# TK90X.net
KiCad netlist of a schematic drawn in EAGLE
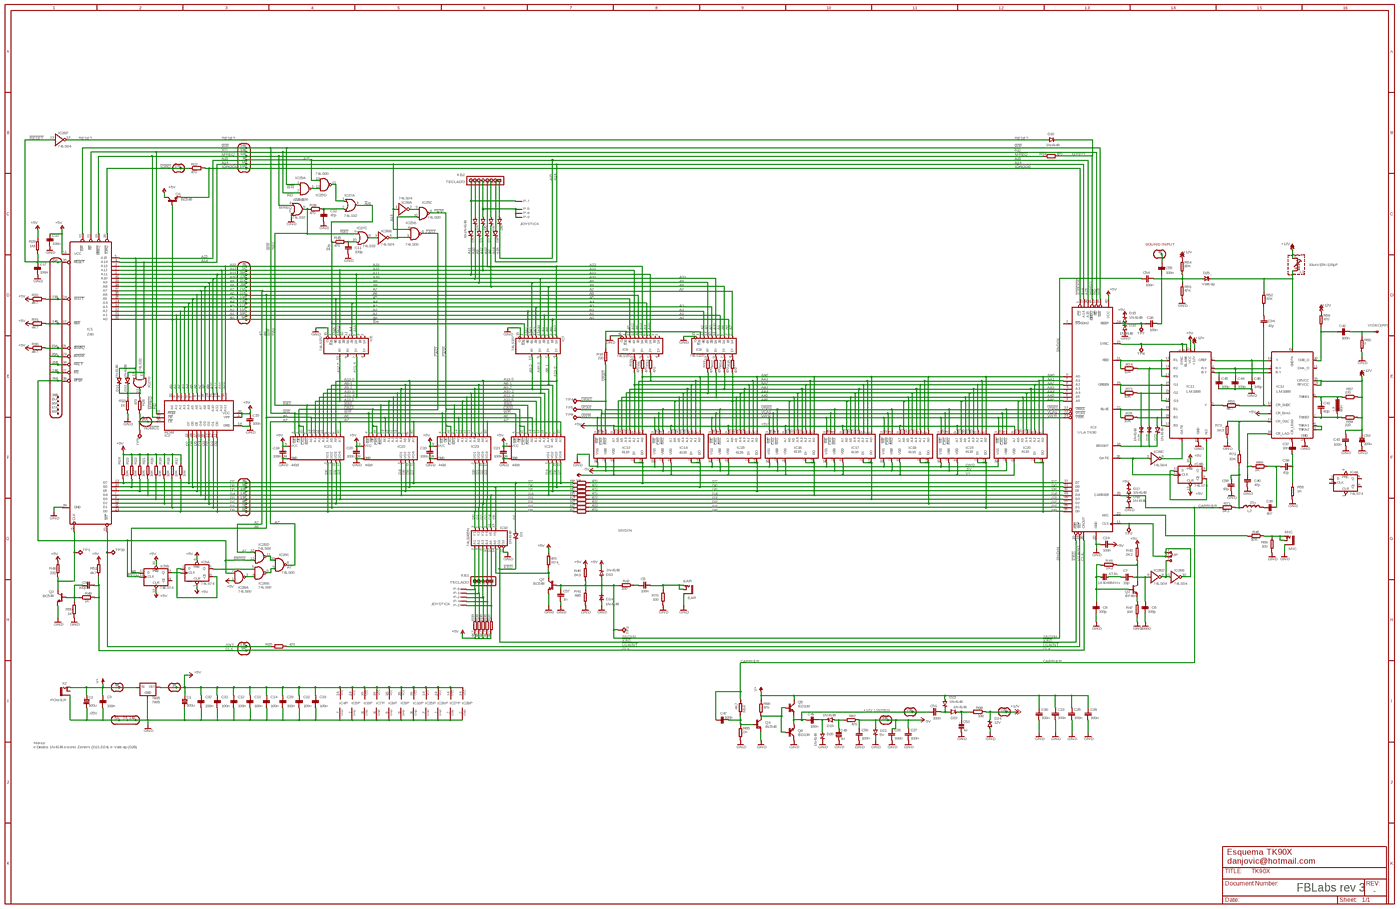
[diagram p0: schematic, sheet 1, overview]
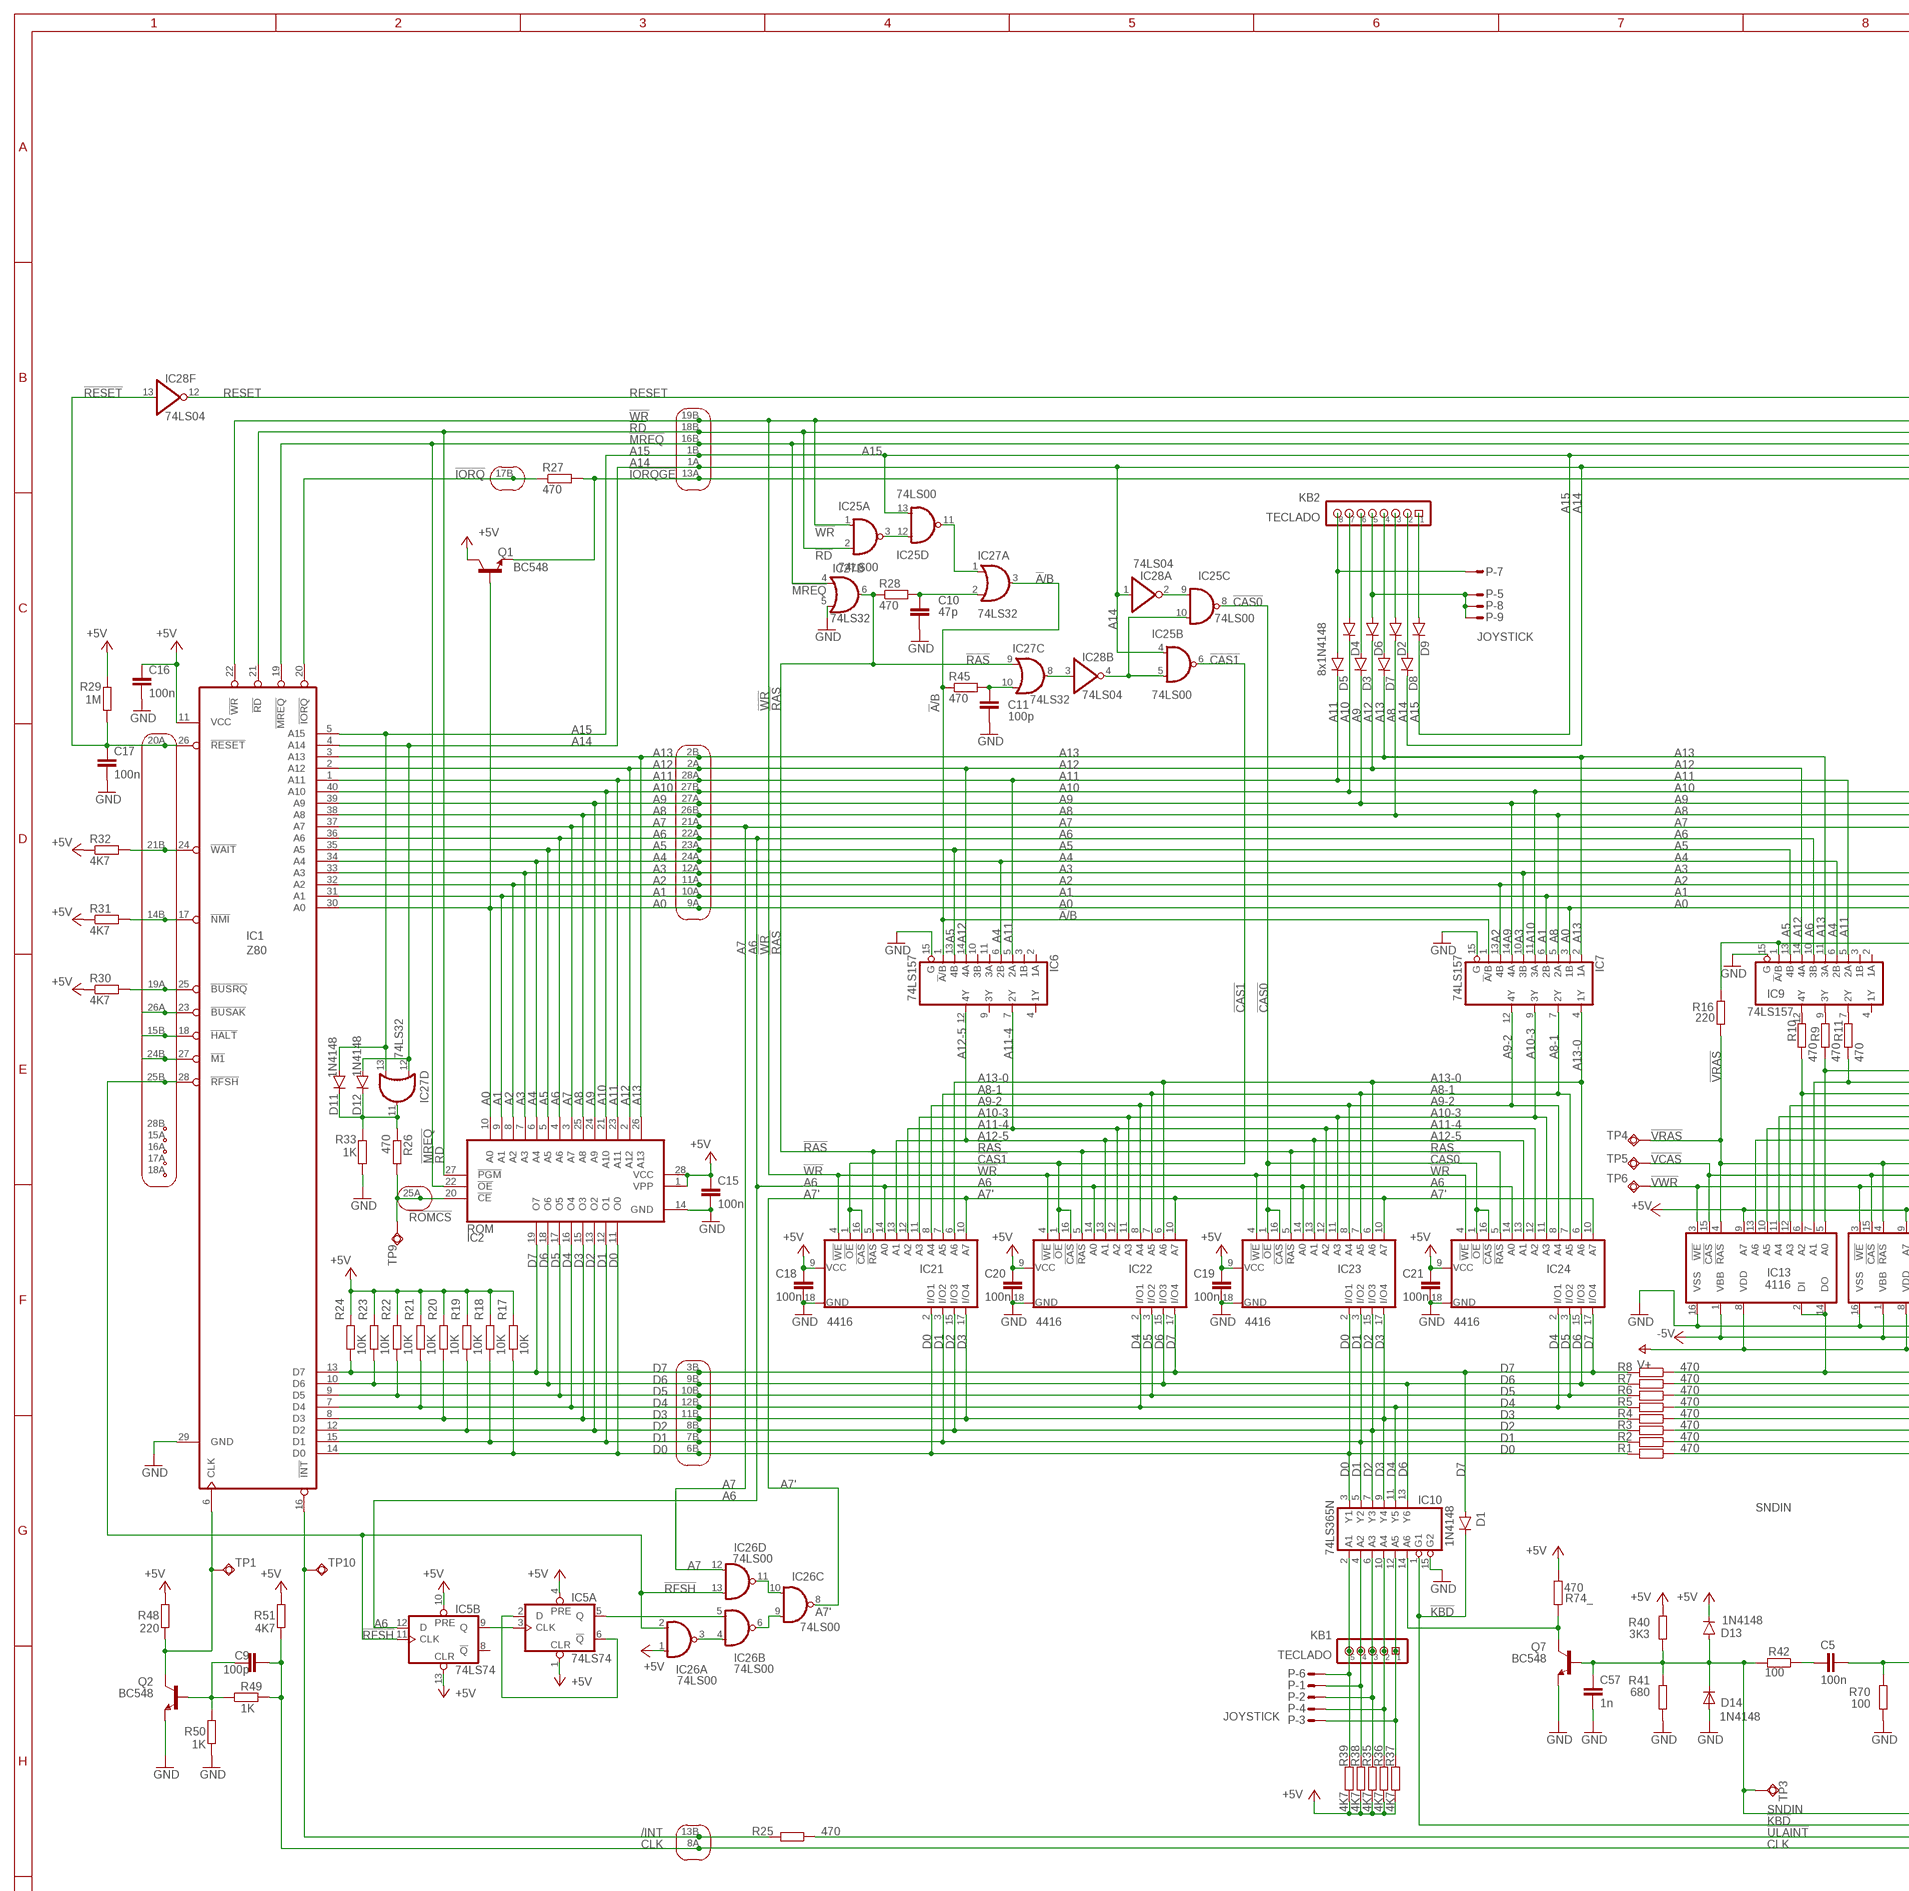
[diagram p1: schematic, sheet 1, part 1 of 4]
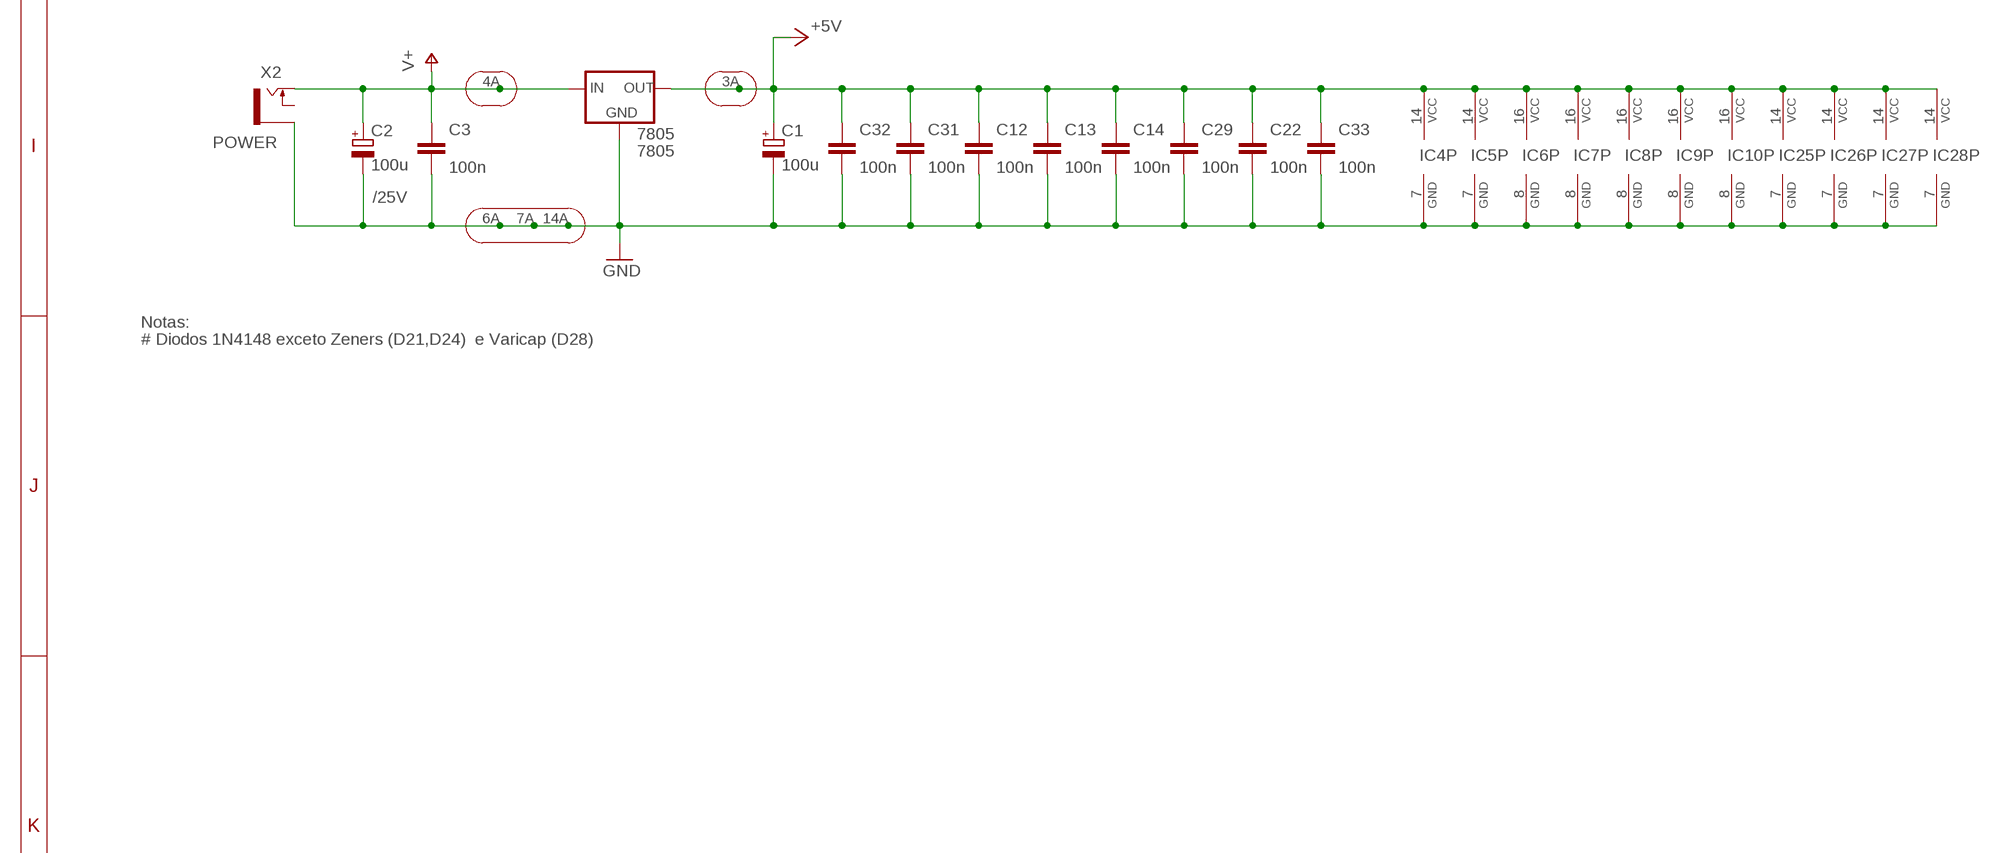
[diagram p2: schematic, sheet 1, part 2 of 4]
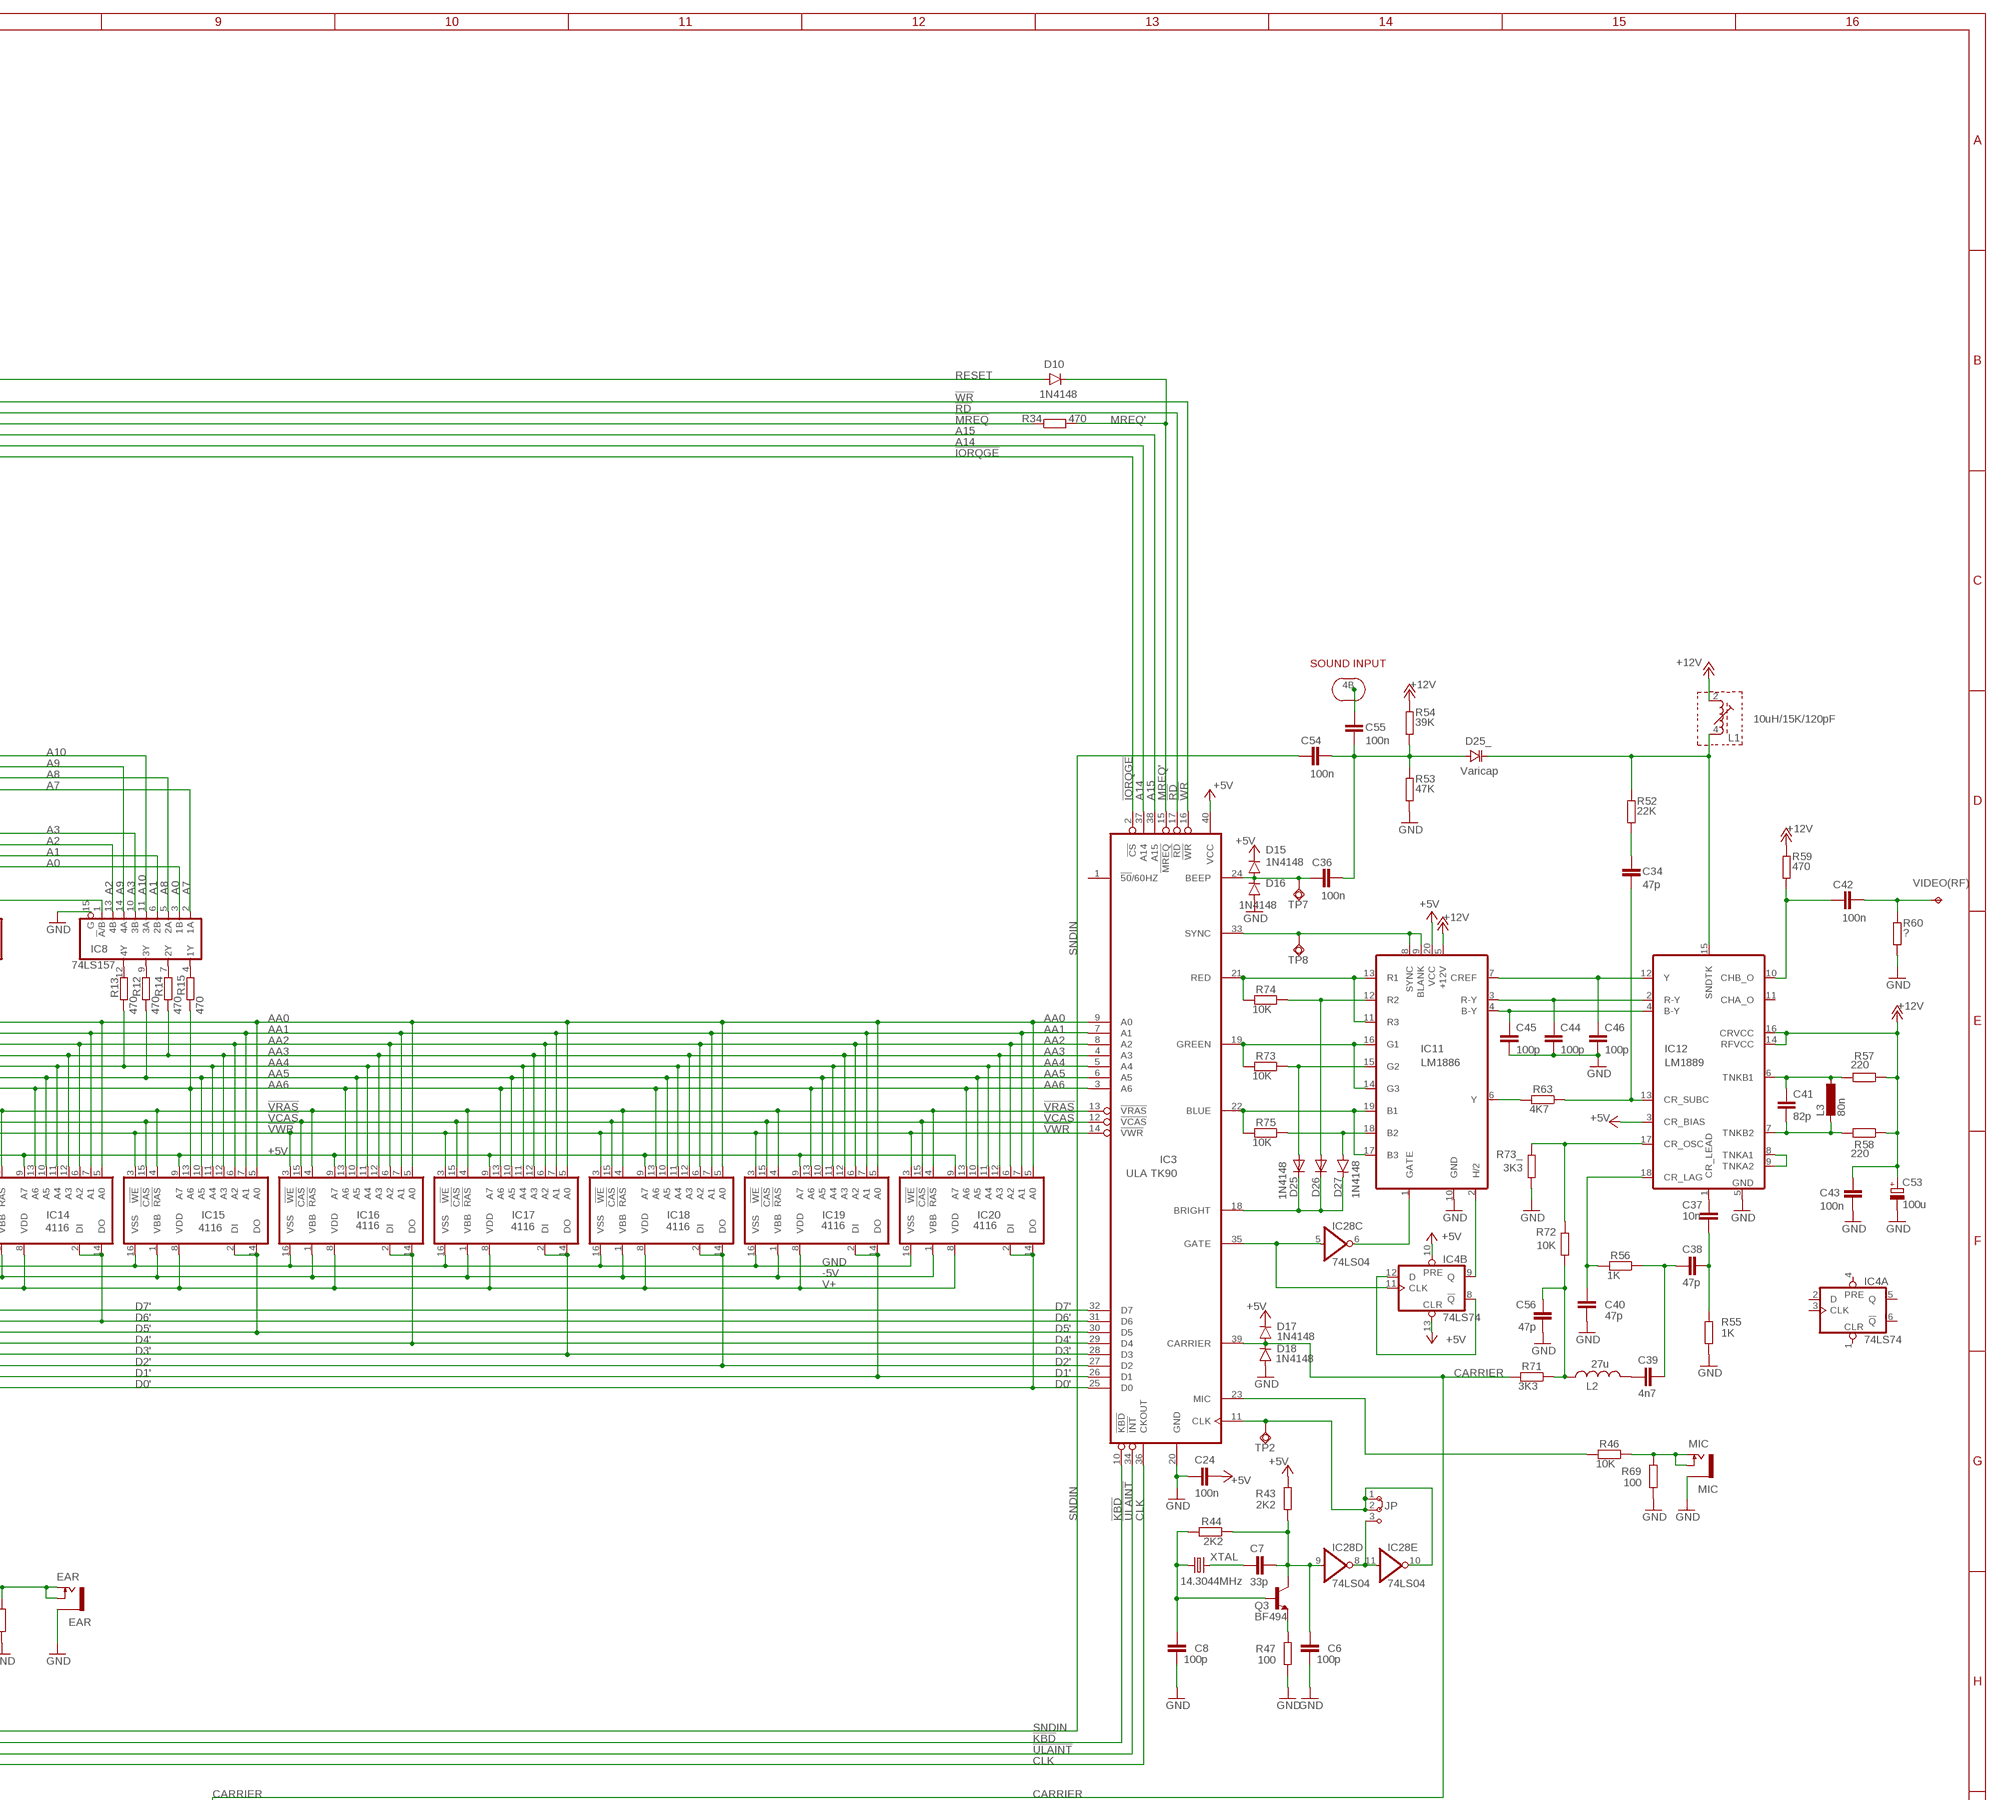
[diagram p3: schematic, sheet 1, part 3 of 4]
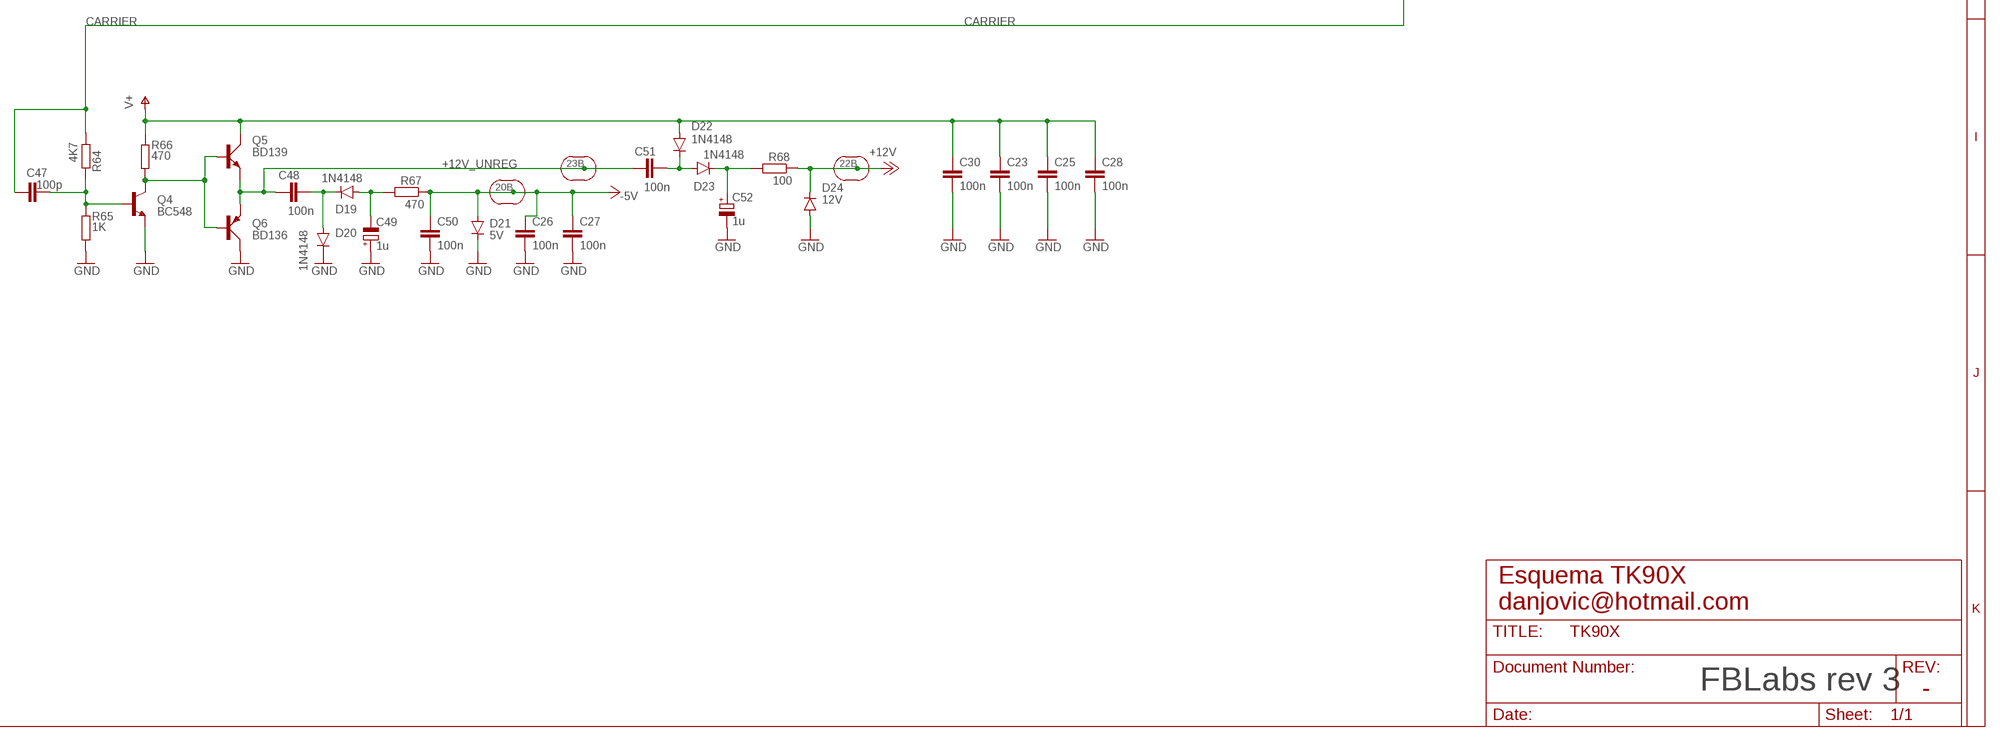
[diagram p4: schematic, sheet 1, part 4 of 4]

(export (version "E")
  (design (tool "Eeschema 10.0.6"))
  (components
    (comp (ref "7805")
      (value "7805")
      (footprint "eagle-import:78XXL")
      (libsource (lib "eagle-import") (part "78XXL"))
    )
    (comp (ref "C1")
      (value "100u")
      (footprint "eagle-import:E5-8,5")
      (libsource (lib "eagle-import") (part "CPOL-EUE5-8.5"))
    )
    (comp (ref "C2")
      (value "100u")
      (footprint "eagle-import:E5-8,5")
      (libsource (lib "eagle-import") (part "CPOL-EUE5-8.5"))
    )
    (comp (ref "C3")
      (value "100n")
      (footprint "eagle-import:C050-024X044")
      (libsource (lib "eagle-import") (part "C-EU050-024X044"))
    )
    (comp (ref "C5")
      (value "100n")
      (footprint "eagle-import:C050-024X044")
      (libsource (lib "eagle-import") (part "C-EU050-024X044"))
    )
    (comp (ref "C6")
      (value "100p")
      (footprint "eagle-import:C050-024X044")
      (libsource (lib "eagle-import") (part "C-EU050-024X044"))
    )
    (comp (ref "C7")
      (value "33p")
      (footprint "eagle-import:C050-024X044")
      (libsource (lib "eagle-import") (part "C-EU050-024X044"))
    )
    (comp (ref "C8")
      (value "100p")
      (footprint "eagle-import:C050-024X044")
      (libsource (lib "eagle-import") (part "C-EU050-024X044"))
    )
    (comp (ref "C9")
      (value "100p")
      (footprint "eagle-import:C050-024X044")
      (libsource (lib "eagle-import") (part "C-EU050-024X044"))
    )
    (comp (ref "C10")
      (value "47p")
      (footprint "eagle-import:C050-024X044")
      (libsource (lib "eagle-import") (part "C-EU050-024X044"))
    )
    (comp (ref "C11")
      (value "100p")
      (footprint "eagle-import:C050-024X044")
      (libsource (lib "eagle-import") (part "C-EU050-024X044"))
    )
    (comp (ref "C12")
      (value "100n")
      (footprint "eagle-import:C050-024X044")
      (libsource (lib "eagle-import") (part "C-EU050-024X044"))
    )
    (comp (ref "C13")
      (value "100n")
      (footprint "eagle-import:C050-024X044")
      (libsource (lib "eagle-import") (part "C-EU050-024X044"))
    )
    (comp (ref "C14")
      (value "100n")
      (footprint "eagle-import:C050-024X044")
      (libsource (lib "eagle-import") (part "C-EU050-024X044"))
    )
    (comp (ref "C15")
      (value "100n")
      (footprint "eagle-import:C050-024X044")
      (libsource (lib "eagle-import") (part "C-EU050-024X044"))
    )
    (comp (ref "C16")
      (value "100n")
      (footprint "eagle-import:C050-024X044")
      (libsource (lib "eagle-import") (part "C-EU050-024X044"))
    )
    (comp (ref "C17")
      (value "100n")
      (footprint "eagle-import:C050-024X044")
      (libsource (lib "eagle-import") (part "C-EU050-024X044"))
    )
    (comp (ref "C18")
      (value "100n")
      (footprint "eagle-import:C050-024X044")
      (libsource (lib "eagle-import") (part "C-EU050-024X044"))
    )
    (comp (ref "C19")
      (value "100n")
      (footprint "eagle-import:C050-024X044")
      (libsource (lib "eagle-import") (part "C-EU050-024X044"))
    )
    (comp (ref "C20")
      (value "100n")
      (footprint "eagle-import:C050-024X044")
      (libsource (lib "eagle-import") (part "C-EU050-024X044"))
    )
    (comp (ref "C21")
      (value "100n")
      (footprint "eagle-import:C050-024X044")
      (libsource (lib "eagle-import") (part "C-EU050-024X044"))
    )
    (comp (ref "C22")
      (value "100n")
      (footprint "eagle-import:C050-024X044")
      (libsource (lib "eagle-import") (part "C-EU050-024X044"))
    )
    (comp (ref "C23")
      (value "100n")
      (footprint "eagle-import:C050-024X044")
      (libsource (lib "eagle-import") (part "C-EU050-024X044"))
    )
    (comp (ref "C24")
      (value "100n")
      (footprint "eagle-import:C050-024X044")
      (libsource (lib "eagle-import") (part "C-EU050-024X044"))
    )
    (comp (ref "C25")
      (value "100n")
      (footprint "eagle-import:C050-024X044")
      (libsource (lib "eagle-import") (part "C-EU050-024X044"))
    )
    (comp (ref "C26")
      (value "100n")
      (footprint "eagle-import:C050-024X044")
      (libsource (lib "eagle-import") (part "C-EU050-024X044"))
    )
    (comp (ref "C27")
      (value "100n")
      (footprint "eagle-import:C050-024X044")
      (libsource (lib "eagle-import") (part "C-EU050-024X044"))
    )
    (comp (ref "C28")
      (value "100n")
      (footprint "eagle-import:C050-024X044")
      (libsource (lib "eagle-import") (part "C-EU050-024X044"))
    )
    (comp (ref "C29")
      (value "100n")
      (footprint "eagle-import:C050-024X044")
      (libsource (lib "eagle-import") (part "C-EU050-024X044"))
    )
    (comp (ref "C30")
      (value "100n")
      (footprint "eagle-import:C050-024X044")
      (libsource (lib "eagle-import") (part "C-EU050-024X044"))
    )
    (comp (ref "C31")
      (value "100n")
      (footprint "eagle-import:C050-024X044")
      (libsource (lib "eagle-import") (part "C-EU050-024X044"))
    )
    (comp (ref "C32")
      (value "100n")
      (footprint "eagle-import:C050-024X044")
      (libsource (lib "eagle-import") (part "C-EU050-024X044"))
    )
    (comp (ref "C33")
      (value "100n")
      (footprint "eagle-import:C050-024X044")
      (libsource (lib "eagle-import") (part "C-EU050-024X044"))
    )
    (comp (ref "C34")
      (value "47p")
      (footprint "eagle-import:C050-024X044")
      (libsource (lib "eagle-import") (part "C-EU050-024X044"))
    )
    (comp (ref "C36")
      (value "100n")
      (footprint "eagle-import:C050-024X044")
      (libsource (lib "eagle-import") (part "C-EU050-024X044"))
    )
    (comp (ref "C37")
      (value "10n")
      (footprint "eagle-import:C050-024X044")
      (libsource (lib "eagle-import") (part "C-EU050-024X044"))
    )
    (comp (ref "C38")
      (value "47p")
      (footprint "eagle-import:C050-024X044")
      (libsource (lib "eagle-import") (part "C-EU050-024X044"))
    )
    (comp (ref "C39")
      (value "4n7")
      (footprint "eagle-import:C050-024X044")
      (libsource (lib "eagle-import") (part "C-EU050-024X044"))
    )
    (comp (ref "C40")
      (value "47p")
      (footprint "eagle-import:C050-024X044")
      (libsource (lib "eagle-import") (part "C-EU050-024X044"))
    )
    (comp (ref "C41")
      (value "82p")
      (footprint "eagle-import:C050-024X044")
      (libsource (lib "eagle-import") (part "C-EU050-024X044"))
    )
    (comp (ref "C42")
      (value "100n")
      (footprint "eagle-import:C050-024X044")
      (libsource (lib "eagle-import") (part "C-EU050-024X044"))
    )
    (comp (ref "C43")
      (value "100n")
      (footprint "eagle-import:C050-024X044")
      (libsource (lib "eagle-import") (part "C-EU050-024X044"))
    )
    (comp (ref "C44")
      (value "100p")
      (footprint "eagle-import:C050-024X044")
      (libsource (lib "eagle-import") (part "C-EU050-024X044"))
    )
    (comp (ref "C45")
      (value "100p")
      (footprint "eagle-import:C050-024X044")
      (libsource (lib "eagle-import") (part "C-EU050-024X044"))
    )
    (comp (ref "C46")
      (value "100p")
      (footprint "eagle-import:C050-024X044")
      (libsource (lib "eagle-import") (part "C-EU050-024X044"))
    )
    (comp (ref "C47")
      (value "100p")
      (footprint "eagle-import:C050-024X044")
      (libsource (lib "eagle-import") (part "C-EU050-024X044"))
    )
    (comp (ref "C48")
      (value "100n")
      (footprint "eagle-import:C050-024X044")
      (libsource (lib "eagle-import") (part "C-EU050-024X044"))
    )
    (comp (ref "C49")
      (value "1u")
      (footprint "eagle-import:E2-4")
      (libsource (lib "eagle-import") (part "CPOL-EUE2-4"))
    )
    (comp (ref "C50")
      (value "100n")
      (footprint "eagle-import:C050-024X044")
      (libsource (lib "eagle-import") (part "C-EU050-024X044"))
    )
    (comp (ref "C51")
      (value "100n")
      (footprint "eagle-import:C050-024X044")
      (libsource (lib "eagle-import") (part "C-EU050-024X044"))
    )
    (comp (ref "C52")
      (value "1u")
      (footprint "eagle-import:E2-5")
      (libsource (lib "eagle-import") (part "CPOL-EUE2-5"))
    )
    (comp (ref "C53")
      (value "100u")
      (footprint "eagle-import:E5-4")
      (libsource (lib "eagle-import") (part "CPOL-EUE5-4"))
    )
    (comp (ref "C54")
      (value "100n")
      (footprint "eagle-import:C050-024X044")
      (libsource (lib "eagle-import") (part "C-EU050-024X044"))
    )
    (comp (ref "C55")
      (value "100n")
      (footprint "eagle-import:C050-024X044")
      (libsource (lib "eagle-import") (part "C-EU050-024X044"))
    )
    (comp (ref "C56")
      (value "47p")
      (footprint "eagle-import:C050-024X044")
      (libsource (lib "eagle-import") (part "C-EU050-024X044"))
    )
    (comp (ref "C57")
      (value "1n")
      (footprint "eagle-import:C050-024X044")
      (libsource (lib "eagle-import") (part "C-EU050-024X044"))
    )
    (comp (ref "D1")
      (value "1N4148")
      (footprint "eagle-import:DO35-12")
      (libsource (lib "eagle-import") (part "DDO35-12"))
    )
    (comp (ref "D2")
      (value "1N4148")
      (footprint "eagle-import:DO35-12")
      (libsource (lib "eagle-import") (part "DDO35-12"))
    )
    (comp (ref "D3")
      (value "1N4148")
      (footprint "eagle-import:DO35-12")
      (libsource (lib "eagle-import") (part "DDO35-12"))
    )
    (comp (ref "D4")
      (value "1N4148")
      (footprint "eagle-import:DO35-12")
      (libsource (lib "eagle-import") (part "DDO35-12"))
    )
    (comp (ref "D5")
      (value "1N4148")
      (footprint "eagle-import:DO35-12")
      (libsource (lib "eagle-import") (part "DDO35-12"))
    )
    (comp (ref "D6")
      (value "1N4148")
      (footprint "eagle-import:DO35-12")
      (libsource (lib "eagle-import") (part "DDO35-12"))
    )
    (comp (ref "D7")
      (value "1N4148")
      (footprint "eagle-import:DO35-12")
      (libsource (lib "eagle-import") (part "DDO35-12"))
    )
    (comp (ref "D8")
      (value "1N4148")
      (footprint "eagle-import:DO35-12")
      (libsource (lib "eagle-import") (part "DDO35-12"))
    )
    (comp (ref "D9")
      (value "1N4148")
      (footprint "eagle-import:DO35-12")
      (libsource (lib "eagle-import") (part "DDO35-12"))
    )
    (comp (ref "D10")
      (value "1N4148")
      (footprint "eagle-import:DO35-12")
      (libsource (lib "eagle-import") (part "DDO35-12"))
    )
    (comp (ref "D11")
      (value "1N4148")
      (footprint "eagle-import:DO35-12")
      (libsource (lib "eagle-import") (part "DDO35-12"))
    )
    (comp (ref "D12")
      (value "1N4148")
      (footprint "eagle-import:DO35-12")
      (libsource (lib "eagle-import") (part "DDO35-12"))
    )
    (comp (ref "D13")
      (value "1N4148")
      (footprint "eagle-import:DO35-12")
      (libsource (lib "eagle-import") (part "DDO35-12"))
    )
    (comp (ref "D14")
      (value "1N4148")
      (footprint "eagle-import:D-5")
      (libsource (lib "eagle-import") (part "DIODE-D-5"))
    )
    (comp (ref "D15")
      (value "1N4148")
      (footprint "eagle-import:DO35-12")
      (libsource (lib "eagle-import") (part "DDO35-12"))
    )
    (comp (ref "D16")
      (value "1N4148")
      (footprint "eagle-import:DO35-12")
      (libsource (lib "eagle-import") (part "DDO35-12"))
    )
    (comp (ref "D17")
      (value "1N4148")
      (footprint "eagle-import:DO35-12")
      (libsource (lib "eagle-import") (part "DDO35-12"))
    )
    (comp (ref "D18")
      (value "1N4148")
      (footprint "eagle-import:DO35-12")
      (libsource (lib "eagle-import") (part "DDO35-12"))
    )
    (comp (ref "D19")
      (value "1N4148")
      (footprint "eagle-import:DO35-12")
      (libsource (lib "eagle-import") (part "DDO35-12"))
    )
    (comp (ref "D20")
      (value "1N4148")
      (footprint "eagle-import:DO35-12")
      (libsource (lib "eagle-import") (part "DDO35-12"))
    )
    (comp (ref "D21")
      (value "5V")
      (footprint "eagle-import:DO35-12")
      (libsource (lib "eagle-import") (part "DDO35-12"))
    )
    (comp (ref "D22")
      (value "1N4148")
      (footprint "eagle-import:DO35-12")
      (libsource (lib "eagle-import") (part "DDO35-12"))
    )
    (comp (ref "D23")
      (value "1N4148")
      (footprint "eagle-import:DO35-12")
      (libsource (lib "eagle-import") (part "DDO35-12"))
    )
    (comp (ref "D24")
      (value "12V")
      (footprint "eagle-import:DO35-12")
      (libsource (lib "eagle-import") (part "DDO35-12"))
    )
    (comp (ref "D25")
      (value "1N4148")
      (footprint "eagle-import:D-5")
      (libsource (lib "eagle-import") (part "DIODE-D-5"))
    )
    (comp (ref "D25_")
      (value "Varicap")
      (footprint "eagle-import:D200")
      (libsource (lib "eagle-import") (part "VARICAP-200"))
    )
    (comp (ref "D26")
      (value "1N4148")
      (footprint "eagle-import:D-5")
      (libsource (lib "eagle-import") (part "DIODE-D-5"))
    )
    (comp (ref "D27")
      (value "1N4148")
      (footprint "eagle-import:DO35-12")
      (libsource (lib "eagle-import") (part "DDO35-12"))
    )
    (comp (ref "EAR")
      (value "EAR")
      (footprint "eagle-import:MONO")
      (libsource (lib "eagle-import") (part "JACK?-MONO"))
    )
    (comp (ref "IC1")
      (value "Z80")
      (footprint "eagle-import:DIL40")
      (libsource (lib "eagle-import") (part "Z80CPU"))
    )
    (comp (ref "IC2")
      (value "ROM")
      (footprint "eagle-import:DIL28")
      (libsource (lib "eagle-import") (part "25128"))
    )
    (comp (ref "IC3")
      (value "ULA TK90")
      (footprint "eagle-import:DIL40")
      (libsource (lib "eagle-import") (part "ULA-TK90"))
    )
    (comp (ref "IC4")
      (value "74LS74")
      (footprint "eagle-import:DIL14")
      (libsource (lib "eagle-import") (part "7474NLS"))
    )
    (comp (ref "IC5")
      (value "74LS74")
      (footprint "eagle-import:DIL14")
      (libsource (lib "eagle-import") (part "7474NLS"))
    )
    (comp (ref "IC6")
      (value "74LS157")
      (footprint "eagle-import:DIL16")
      (libsource (lib "eagle-import") (part "74157NS"))
    )
    (comp (ref "IC7")
      (value "74LS157")
      (footprint "eagle-import:DIL16")
      (libsource (lib "eagle-import") (part "74157NS"))
    )
    (comp (ref "IC8")
      (value "74LS157")
      (footprint "eagle-import:DIL16")
      (libsource (lib "eagle-import") (part "74157NS"))
    )
    (comp (ref "IC9")
      (value "74LS157")
      (footprint "eagle-import:DIL16")
      (libsource (lib "eagle-import") (part "74157NS"))
    )
    (comp (ref "IC10")
      (value "74LS365N")
      (footprint "eagle-import:DIL16")
      (libsource (lib "eagle-import") (part "74365NLS"))
    )
    (comp (ref "IC11")
      (value "LM1886")
      (footprint "eagle-import:DIL20")
      (libsource (lib "eagle-import") (part "LM1886N"))
    )
    (comp (ref "IC12")
      (value "LM1889")
      (footprint "eagle-import:DIL18")
      (libsource (lib "eagle-import") (part "LM1889"))
    )
    (comp (ref "IC13")
      (value "4116")
      (footprint "eagle-import:DIL16")
      (libsource (lib "eagle-import") (part "MK4516"))
    )
    (comp (ref "IC14")
      (value "4116")
      (footprint "eagle-import:DIL16")
      (libsource (lib "eagle-import") (part "MK4516"))
    )
    (comp (ref "IC15")
      (value "4116")
      (footprint "eagle-import:DIL16")
      (libsource (lib "eagle-import") (part "MK4516"))
    )
    (comp (ref "IC16")
      (value "4116")
      (footprint "eagle-import:DIL16")
      (libsource (lib "eagle-import") (part "MK4516"))
    )
    (comp (ref "IC17")
      (value "4116")
      (footprint "eagle-import:DIL16")
      (libsource (lib "eagle-import") (part "MK4516"))
    )
    (comp (ref "IC18")
      (value "4116")
      (footprint "eagle-import:DIL16")
      (libsource (lib "eagle-import") (part "MK4516"))
    )
    (comp (ref "IC19")
      (value "4116")
      (footprint "eagle-import:DIL16")
      (libsource (lib "eagle-import") (part "MK4516"))
    )
    (comp (ref "IC20")
      (value "4116")
      (footprint "eagle-import:DIL16")
      (libsource (lib "eagle-import") (part "MK4516"))
    )
    (comp (ref "IC21")
      (value "4416")
      (footprint "eagle-import:DIL18")
      (libsource (lib "eagle-import") (part "4416"))
    )
    (comp (ref "IC22")
      (value "4416")
      (footprint "eagle-import:DIL18")
      (libsource (lib "eagle-import") (part "4416"))
    )
    (comp (ref "IC23")
      (value "4416")
      (footprint "eagle-import:DIL18")
      (libsource (lib "eagle-import") (part "4416"))
    )
    (comp (ref "IC24")
      (value "4416")
      (footprint "eagle-import:DIL18")
      (libsource (lib "eagle-import") (part "4416"))
    )
    (comp (ref "IC25")
      (value "74LS00")
      (footprint "eagle-import:DIL14")
      (libsource (lib "eagle-import") (part "7400NLS"))
    )
    (comp (ref "IC26")
      (value "74LS00")
      (footprint "eagle-import:DIL14")
      (libsource (lib "eagle-import") (part "7400NLS"))
    )
    (comp (ref "IC27")
      (value "74LS32")
      (footprint "eagle-import:DIL14")
      (libsource (lib "eagle-import") (part "7432NLS"))
    )
    (comp (ref "IC28")
      (value "74LS04")
      (footprint "eagle-import:DIL14")
      (libsource (lib "eagle-import") (part "7404NLS"))
    )
    (comp (ref "JP")
      (value "J2X1MM")
      (footprint "eagle-import:03C")
      (libsource (lib "eagle-import") (part "J2X1MM"))
    )
    (comp (ref "KB1")
      (value "TECLADO")
      (footprint "eagle-import:FE05-1")
      (libsource (lib "eagle-import") (part "CON-TECL-5"))
    )
    (comp (ref "KB2")
      (value "TECLADO")
      (footprint "eagle-import:FE08")
      (libsource (lib "eagle-import") (part "CON-TECL-8"))
    )
    (comp (ref "L1")
      (value "10uH/15K/120pF")
      (footprint "eagle-import:COIL")
      (libsource (lib "eagle-import") (part "COIL"))
    )
    (comp (ref "L2")
      (value "27u")
      (footprint "eagle-import:0207_7")
      (libsource (lib "eagle-import") (part "L-US0207/7"))
    )
    (comp (ref "L3")
      (value "80n")
      (footprint "eagle-import:0204_5")
      (libsource (lib "eagle-import") (part "L-EU0204/5"))
    )
    (comp (ref "MIC")
      (value "MIC")
      (footprint "eagle-import:MONO")
      (libsource (lib "eagle-import") (part "JACK?-MONO"))
    )
    (comp (ref "P")
      (value "JOYSTICK")
      (footprint "eagle-import:177-009-MALE")
      (libsource (lib "eagle-import") (part "M09?S.590"))
    )
    (comp (ref "Q1")
      (value "BC548")
      (footprint "eagle-import:TO92L")
      (libsource (lib "eagle-import") (part "-NPN-TO92L"))
    )
    (comp (ref "Q2")
      (value "BC548")
      (footprint "eagle-import:TO92L")
      (libsource (lib "eagle-import") (part "-NPN-TO92L"))
    )
    (comp (ref "Q3")
      (value "BF494")
      (footprint "eagle-import:TO92-CEB")
      (libsource (lib "eagle-import") (part "BF494"))
    )
    (comp (ref "Q4")
      (value "BC548")
      (footprint "eagle-import:TO92L")
      (libsource (lib "eagle-import") (part "-NPN-TO92L"))
    )
    (comp (ref "Q5")
      (value "BD139")
      (footprint "eagle-import:TO126AV")
      (libsource (lib "eagle-import") (part "BD139"))
    )
    (comp (ref "Q6")
      (value "BD136")
      (footprint "eagle-import:TO126AV")
      (libsource (lib "eagle-import") (part "BD140"))
    )
    (comp (ref "Q7")
      (value "BC548")
      (footprint "eagle-import:TO92L")
      (libsource (lib "eagle-import") (part "-NPN-TO92L"))
    )
    (comp (ref "R1")
      (value "470")
      (footprint "eagle-import:0207_12")
      (libsource (lib "eagle-import") (part "R-EU_0207/12"))
    )
    (comp (ref "R2")
      (value "470")
      (footprint "eagle-import:0207_12")
      (libsource (lib "eagle-import") (part "R-EU_0207/12"))
    )
    (comp (ref "R3")
      (value "470")
      (footprint "eagle-import:0207_12")
      (libsource (lib "eagle-import") (part "R-EU_0207/12"))
    )
    (comp (ref "R4")
      (value "470")
      (footprint "eagle-import:0207_12")
      (libsource (lib "eagle-import") (part "R-EU_0207/12"))
    )
    (comp (ref "R5")
      (value "470")
      (footprint "eagle-import:0207_12")
      (libsource (lib "eagle-import") (part "R-EU_0207/12"))
    )
    (comp (ref "R6")
      (value "470")
      (footprint "eagle-import:0207_12")
      (libsource (lib "eagle-import") (part "R-EU_0207/12"))
    )
    (comp (ref "R7")
      (value "470")
      (footprint "eagle-import:0207_12")
      (libsource (lib "eagle-import") (part "R-EU_0207/12"))
    )
    (comp (ref "R8")
      (value "470")
      (footprint "eagle-import:0207_12")
      (libsource (lib "eagle-import") (part "R-EU_0207/12"))
    )
    (comp (ref "R9")
      (value "470")
      (footprint "eagle-import:0207_12")
      (libsource (lib "eagle-import") (part "R-EU_0207/12"))
    )
    (comp (ref "R10")
      (value "470")
      (footprint "eagle-import:0207_12")
      (libsource (lib "eagle-import") (part "R-EU_0207/12"))
    )
    (comp (ref "R11")
      (value "470")
      (footprint "eagle-import:0207_12")
      (libsource (lib "eagle-import") (part "R-EU_0207/12"))
    )
    (comp (ref "R12")
      (value "470")
      (footprint "eagle-import:0207_12")
      (libsource (lib "eagle-import") (part "R-EU_0207/12"))
    )
    (comp (ref "R13")
      (value "470")
      (footprint "eagle-import:0207_12")
      (libsource (lib "eagle-import") (part "R-EU_0207/12"))
    )
    (comp (ref "R14")
      (value "470")
      (footprint "eagle-import:0207_12")
      (libsource (lib "eagle-import") (part "R-EU_0207/12"))
    )
    (comp (ref "R15")
      (value "470")
      (footprint "eagle-import:0207_12")
      (libsource (lib "eagle-import") (part "R-EU_0207/12"))
    )
    (comp (ref "R16")
      (value "220")
      (footprint "eagle-import:0207_12")
      (libsource (lib "eagle-import") (part "R-EU_0207/12"))
    )
    (comp (ref "R17")
      (value "10K")
      (footprint "eagle-import:0207_12")
      (libsource (lib "eagle-import") (part "R-EU_0207/12"))
    )
    (comp (ref "R18")
      (value "10K")
      (footprint "eagle-import:0207_12")
      (libsource (lib "eagle-import") (part "R-EU_0207/12"))
    )
    (comp (ref "R19")
      (value "10K")
      (footprint "eagle-import:0207_12")
      (libsource (lib "eagle-import") (part "R-EU_0207/12"))
    )
    (comp (ref "R20")
      (value "10K")
      (footprint "eagle-import:0207_12")
      (libsource (lib "eagle-import") (part "R-EU_0207/12"))
    )
    (comp (ref "R21")
      (value "10K")
      (footprint "eagle-import:0207_12")
      (libsource (lib "eagle-import") (part "R-EU_0207/12"))
    )
    (comp (ref "R22")
      (value "10K")
      (footprint "eagle-import:0207_12")
      (libsource (lib "eagle-import") (part "R-EU_0207/12"))
    )
    (comp (ref "R23")
      (value "10K")
      (footprint "eagle-import:0207_12")
      (libsource (lib "eagle-import") (part "R-EU_0207/12"))
    )
    (comp (ref "R24")
      (value "10K")
      (footprint "eagle-import:0207_12")
      (libsource (lib "eagle-import") (part "R-EU_0207/12"))
    )
    (comp (ref "R25")
      (value "470")
      (footprint "eagle-import:0207_12")
      (libsource (lib "eagle-import") (part "R-EU_0207/12"))
    )
    (comp (ref "R26")
      (value "470")
      (footprint "eagle-import:0207_12")
      (libsource (lib "eagle-import") (part "R-EU_0207/12"))
    )
    (comp (ref "R27")
      (value "470")
      (footprint "eagle-import:0207_12")
      (libsource (lib "eagle-import") (part "R-EU_0207/12"))
    )
    (comp (ref "R28")
      (value "470")
      (footprint "eagle-import:0207_12")
      (libsource (lib "eagle-import") (part "R-EU_0207/12"))
    )
    (comp (ref "R29")
      (value "1M")
      (footprint "eagle-import:0207_12")
      (libsource (lib "eagle-import") (part "R-EU_0207/12"))
    )
    (comp (ref "R30")
      (value "4K7")
      (footprint "eagle-import:0207_12")
      (libsource (lib "eagle-import") (part "R-EU_0207/12"))
    )
    (comp (ref "R31")
      (value "4K7")
      (footprint "eagle-import:0207_12")
      (libsource (lib "eagle-import") (part "R-EU_0207/12"))
    )
    (comp (ref "R32")
      (value "4K7")
      (footprint "eagle-import:0207_12")
      (libsource (lib "eagle-import") (part "R-EU_0207/12"))
    )
    (comp (ref "R33")
      (value "1K")
      (footprint "eagle-import:0207_12")
      (libsource (lib "eagle-import") (part "R-EU_0207/12"))
    )
    (comp (ref "R34")
      (value "470")
      (footprint "eagle-import:0207_12")
      (libsource (lib "eagle-import") (part "R-EU_0207/12"))
    )
    (comp (ref "R35")
      (value "4K7")
      (footprint "eagle-import:0207_12")
      (libsource (lib "eagle-import") (part "R-EU_0207/12"))
    )
    (comp (ref "R36")
      (value "4K7")
      (footprint "eagle-import:0207_12")
      (libsource (lib "eagle-import") (part "R-EU_0207/12"))
    )
    (comp (ref "R37")
      (value "4K7")
      (footprint "eagle-import:0207_12")
      (libsource (lib "eagle-import") (part "R-EU_0207/12"))
    )
    (comp (ref "R38")
      (value "4K7")
      (footprint "eagle-import:0207_12")
      (libsource (lib "eagle-import") (part "R-EU_0207/12"))
    )
    (comp (ref "R39")
      (value "4K7")
      (footprint "eagle-import:0207_12")
      (libsource (lib "eagle-import") (part "R-EU_0207/12"))
    )
    (comp (ref "R40")
      (value "3K3")
      (footprint "eagle-import:0207_12")
      (libsource (lib "eagle-import") (part "R-EU_0207/12"))
    )
    (comp (ref "R41")
      (value "680")
      (footprint "eagle-import:0207_5V")
      (libsource (lib "eagle-import") (part "R-EU_0207/5V"))
    )
    (comp (ref "R42")
      (value "100")
      (footprint "eagle-import:0207_5V")
      (libsource (lib "eagle-import") (part "R-EU_0207/5V"))
    )
    (comp (ref "R43")
      (value "2K2")
      (footprint "eagle-import:0207_12")
      (libsource (lib "eagle-import") (part "R-EU_0207/12"))
    )
    (comp (ref "R44")
      (value "2K2")
      (footprint "eagle-import:0207_12")
      (libsource (lib "eagle-import") (part "R-EU_0207/12"))
    )
    (comp (ref "R45")
      (value "470")
      (footprint "eagle-import:0207_12")
      (libsource (lib "eagle-import") (part "R-EU_0207/12"))
    )
    (comp (ref "R46")
      (value "10K")
      (footprint "eagle-import:0207_12")
      (libsource (lib "eagle-import") (part "R-EU_0207/12"))
    )
    (comp (ref "R47")
      (value "100")
      (footprint "eagle-import:0207_12")
      (libsource (lib "eagle-import") (part "R-EU_0207/12"))
    )
    (comp (ref "R48")
      (value "220")
      (footprint "eagle-import:0207_12")
      (libsource (lib "eagle-import") (part "R-EU_0207/12"))
    )
    (comp (ref "R49")
      (value "1K")
      (footprint "eagle-import:0207_12")
      (libsource (lib "eagle-import") (part "R-EU_0207/12"))
    )
    (comp (ref "R50")
      (value "1K")
      (footprint "eagle-import:0207_12")
      (libsource (lib "eagle-import") (part "R-EU_0207/12"))
    )
    (comp (ref "R51")
      (value "4K7")
      (footprint "eagle-import:0207_12")
      (libsource (lib "eagle-import") (part "R-EU_0207/12"))
    )
    (comp (ref "R52")
      (value "22K")
      (footprint "eagle-import:0207_5V")
      (libsource (lib "eagle-import") (part "R-EU_0207/5V"))
    )
    (comp (ref "R53")
      (value "47K")
      (footprint "eagle-import:0207_12")
      (libsource (lib "eagle-import") (part "R-EU_0207/12"))
    )
    (comp (ref "R54")
      (value "39K")
      (footprint "eagle-import:0207_12")
      (libsource (lib "eagle-import") (part "R-EU_0207/12"))
    )
    (comp (ref "R55")
      (value "1K")
      (footprint "eagle-import:0207_5V")
      (libsource (lib "eagle-import") (part "R-EU_0207/5V"))
    )
    (comp (ref "R56")
      (value "1K")
      (footprint "eagle-import:0207_5V")
      (libsource (lib "eagle-import") (part "R-EU_0207/5V"))
    )
    (comp (ref "R57")
      (value "220")
      (footprint "eagle-import:0207_5V")
      (libsource (lib "eagle-import") (part "R-EU_0207/5V"))
    )
    (comp (ref "R58")
      (value "220")
      (footprint "eagle-import:0207_5V")
      (libsource (lib "eagle-import") (part "R-EU_0207/5V"))
    )
    (comp (ref "R59")
      (value "470")
      (footprint "eagle-import:0207_5V")
      (libsource (lib "eagle-import") (part "R-EU_0207/5V"))
    )
    (comp (ref "R60")
      (value "?")
      (footprint "eagle-import:0207_5V")
      (libsource (lib "eagle-import") (part "R-EU_0207/5V"))
    )
    (comp (ref "R63")
      (value "4K7")
      (footprint "eagle-import:0207_12")
      (libsource (lib "eagle-import") (part "R-EU_0207/12"))
    )
    (comp (ref "R64")
      (value "4K7")
      (footprint "eagle-import:0207_12")
      (libsource (lib "eagle-import") (part "R-EU_0207/12"))
    )
    (comp (ref "R65")
      (value "1K")
      (footprint "eagle-import:0207_12")
      (libsource (lib "eagle-import") (part "R-EU_0207/12"))
    )
    (comp (ref "R66")
      (value "470")
      (footprint "eagle-import:0207_12")
      (libsource (lib "eagle-import") (part "R-EU_0207/12"))
    )
    (comp (ref "R67")
      (value "470")
      (footprint "eagle-import:0207_12")
      (libsource (lib "eagle-import") (part "R-EU_0207/12"))
    )
    (comp (ref "R68")
      (value "100")
      (footprint "eagle-import:0207_12")
      (libsource (lib "eagle-import") (part "R-EU_0207/12"))
    )
    (comp (ref "R69")
      (value "100")
      (footprint "eagle-import:0207_5V")
      (libsource (lib "eagle-import") (part "R-EU_0207/5V"))
    )
    (comp (ref "R70")
      (value "100")
      (footprint "eagle-import:0207_5V")
      (libsource (lib "eagle-import") (part "R-EU_0207/5V"))
    )
    (comp (ref "R71")
      (value "3K3")
      (footprint "eagle-import:0207_5V")
      (libsource (lib "eagle-import") (part "R-EU_0207/5V"))
    )
    (comp (ref "R72")
      (value "10K")
      (footprint "eagle-import:0207_5V")
      (libsource (lib "eagle-import") (part "R-EU_0207/5V"))
    )
    (comp (ref "R73")
      (value "10K")
      (footprint "eagle-import:0207_5V")
      (libsource (lib "eagle-import") (part "R-EU_0207/5V"))
    )
    (comp (ref "R73_")
      (value "3K3")
      (footprint "eagle-import:0207_12")
      (libsource (lib "eagle-import") (part "R-EU_0207/12"))
    )
    (comp (ref "R74")
      (value "10K")
      (footprint "eagle-import:0207_5V")
      (libsource (lib "eagle-import") (part "R-EU_0207/5V"))
    )
    (comp (ref "R74_")
      (value "470")
      (footprint "eagle-import:0207_12")
      (libsource (lib "eagle-import") (part "R-EU_0207/12"))
    )
    (comp (ref "R75")
      (value "10K")
      (footprint "eagle-import:0207_12")
      (libsource (lib "eagle-import") (part "R-EU_0207/12"))
    )
    (comp (ref "TP1")
      (value "TPSQPAD1-13")
      (footprint "eagle-import:P1-13")
      (libsource (lib "eagle-import") (part "TPSQPAD1-13"))
    )
    (comp (ref "TP2")
      (value "TPSQPAD1-13")
      (footprint "eagle-import:P1-13")
      (libsource (lib "eagle-import") (part "TPSQPAD1-13"))
    )
    (comp (ref "TP3")
      (value "TPSQPAD1-13")
      (footprint "eagle-import:P1-13")
      (libsource (lib "eagle-import") (part "TPSQPAD1-13"))
    )
    (comp (ref "TP4")
      (value "TPSQPAD1-13")
      (footprint "eagle-import:P1-13")
      (libsource (lib "eagle-import") (part "TPSQPAD1-13"))
    )
    (comp (ref "TP5")
      (value "TPSQPAD1-13")
      (footprint "eagle-import:P1-13")
      (libsource (lib "eagle-import") (part "TPSQPAD1-13"))
    )
    (comp (ref "TP6")
      (value "TPSQPAD1-13")
      (footprint "eagle-import:P1-13")
      (libsource (lib "eagle-import") (part "TPSQPAD1-13"))
    )
    (comp (ref "TP7")
      (value "TPSQPAD1-13")
      (footprint "eagle-import:P1-13")
      (libsource (lib "eagle-import") (part "TPSQPAD1-13"))
    )
    (comp (ref "TP8")
      (value "TPSQPAD1-13")
      (footprint "eagle-import:P1-13")
      (libsource (lib "eagle-import") (part "TPSQPAD1-13"))
    )
    (comp (ref "TP9")
      (value "TPSQPAD1-13")
      (footprint "eagle-import:P1-13")
      (libsource (lib "eagle-import") (part "TPSQPAD1-13"))
    )
    (comp (ref "TP10")
      (value "TPSQPAD1-13")
      (footprint "eagle-import:P1-13")
      (libsource (lib "eagle-import") (part "TPSQPAD1-13"))
    )
    (comp (ref "U$1")
      (value "TK90_EDGE")
      (footprint "eagle-import:TK-EDGE")
      (libsource (lib "eagle-import") (part "TK90_EDGE"))
    )
    (comp (ref "VIDEO(RF)")
      (value "RF")
      (footprint "eagle-import:P1-13")
      (libsource (lib "eagle-import") (part "TPPAD1-13"))
    )
    (comp (ref "X2")
      (value "POWER")
      (footprint "eagle-import:MONO")
      (libsource (lib "eagle-import") (part "JACK?-MONO"))
    )
    (comp (ref "XTAL")
      (value "14.3044MHz")
      (footprint "eagle-import:HC49_S")
      (libsource (lib "eagle-import") (part "CRYSTALHC49S"))
    )
  )
  (nets
    (net (code "1") (name "+5V") (class "Default")
      (node (ref "7805") (pin "OUT") (pinfunction "OUT_OUT") (pintype "passive"))
      (node (ref "C1") (pin "+") (pinfunction "+_+") (pintype "passive"))
      (node (ref "C12") (pin "2") (pinfunction "2_2") (pintype "passive"))
      (node (ref "C13") (pin "2") (pinfunction "2_2") (pintype "passive"))
      (node (ref "C14") (pin "2") (pinfunction "2_2") (pintype "passive"))
      (node (ref "C15") (pin "1") (pinfunction "1_1") (pintype "passive"))
      (node (ref "C16") (pin "1") (pinfunction "1_1") (pintype "passive"))
      (node (ref "C18") (pin "1") (pinfunction "1_1") (pintype "passive"))
      (node (ref "C19") (pin "1") (pinfunction "1_1") (pintype "passive"))
      (node (ref "C20") (pin "1") (pinfunction "1_1") (pintype "passive"))
      (node (ref "C21") (pin "1") (pinfunction "1_1") (pintype "passive"))
      (node (ref "C22") (pin "2") (pinfunction "2_2") (pintype "passive"))
      (node (ref "C24") (pin "2") (pinfunction "2_2") (pintype "passive"))
      (node (ref "C29") (pin "2") (pinfunction "2_2") (pintype "passive"))
      (node (ref "C31") (pin "2") (pinfunction "2_2") (pintype "passive"))
      (node (ref "C32") (pin "2") (pinfunction "2_2") (pintype "passive"))
      (node (ref "C33") (pin "2") (pinfunction "2_2") (pintype "passive"))
      (node (ref "D13") (pin "C") (pinfunction "K_C") (pintype "bidirectional"))
      (node (ref "D15") (pin "C") (pinfunction "K_C") (pintype "bidirectional"))
      (node (ref "D17") (pin "C") (pinfunction "K_C") (pintype "bidirectional"))
      (node (ref "IC1") (pin "11") (pinfunction "VCC_11") (pintype "power_in"))
      (node (ref "IC10") (pin "16") (pinfunction "VCC_16") (pintype "power_in"))
      (node (ref "IC11") (pin "20") (pinfunction "VCC_20") (pintype "power_in"))
      (node (ref "IC12") (pin "3") (pinfunction "CR_BIAS_3") (pintype "input"))
      (node (ref "IC13") (pin "9") (pinfunction "A7_9") (pintype "input"))
      (node (ref "IC14") (pin "9") (pinfunction "A7_9") (pintype "input"))
      (node (ref "IC15") (pin "9") (pinfunction "A7_9") (pintype "input"))
      (node (ref "IC16") (pin "9") (pinfunction "A7_9") (pintype "input"))
      (node (ref "IC17") (pin "9") (pinfunction "A7_9") (pintype "input"))
      (node (ref "IC18") (pin "9") (pinfunction "A7_9") (pintype "input"))
      (node (ref "IC19") (pin "9") (pinfunction "A7_9") (pintype "input"))
      (node (ref "IC2") (pin "1") (pinfunction "VPP_1") (pintype "input"))
      (node (ref "IC2") (pin "28") (pinfunction "VCC_28") (pintype "power_in"))
      (node (ref "IC20") (pin "9") (pinfunction "A7_9") (pintype "input"))
      (node (ref "IC21") (pin "9") (pinfunction "VCC_9") (pintype "power_in"))
      (node (ref "IC22") (pin "9") (pinfunction "VCC_9") (pintype "power_in"))
      (node (ref "IC23") (pin "9") (pinfunction "VCC_9") (pintype "power_in"))
      (node (ref "IC24") (pin "9") (pinfunction "VCC_9") (pintype "power_in"))
      (node (ref "IC25") (pin "14") (pinfunction "VCC_14") (pintype "power_in"))
      (node (ref "IC26") (pin "1") (pinfunction "I0_1") (pintype "input"))
      (node (ref "IC26") (pin "14") (pinfunction "VCC_14") (pintype "power_in"))
      (node (ref "IC27") (pin "14") (pinfunction "VCC_14") (pintype "power_in"))
      (node (ref "IC28") (pin "14") (pinfunction "VCC_14") (pintype "power_in"))
      (node (ref "IC3") (pin "40") (pinfunction "VCC_40") (pintype "power_in"))
      (node (ref "IC4") (pin "10") (pinfunction "PRE_10") (pintype "input"))
      (node (ref "IC4") (pin "13") (pinfunction "CLR_13") (pintype "input"))
      (node (ref "IC4") (pin "14") (pinfunction "VCC_14") (pintype "power_in"))
      (node (ref "IC5") (pin "1") (pinfunction "CLR_1") (pintype "input"))
      (node (ref "IC5") (pin "10") (pinfunction "PRE_10") (pintype "input"))
      (node (ref "IC5") (pin "13") (pinfunction "CLR_13") (pintype "input"))
      (node (ref "IC5") (pin "14") (pinfunction "VCC_14") (pintype "power_in"))
      (node (ref "IC5") (pin "4") (pinfunction "PRE_4") (pintype "input"))
      (node (ref "IC6") (pin "16") (pinfunction "VCC_16") (pintype "power_in"))
      (node (ref "IC7") (pin "16") (pinfunction "VCC_16") (pintype "power_in"))
      (node (ref "IC8") (pin "16") (pinfunction "VCC_16") (pintype "power_in"))
      (node (ref "IC9") (pin "16") (pinfunction "VCC_16") (pintype "power_in"))
      (node (ref "Q1") (pin "3") (pinfunction "C_3") (pintype "passive"))
      (node (ref "R17") (pin "2") (pinfunction "2_2") (pintype "passive"))
      (node (ref "R18") (pin "2") (pinfunction "2_2") (pintype "passive"))
      (node (ref "R19") (pin "2") (pinfunction "2_2") (pintype "passive"))
      (node (ref "R20") (pin "2") (pinfunction "2_2") (pintype "passive"))
      (node (ref "R21") (pin "2") (pinfunction "2_2") (pintype "passive"))
      (node (ref "R22") (pin "2") (pinfunction "2_2") (pintype "passive"))
      (node (ref "R23") (pin "2") (pinfunction "2_2") (pintype "passive"))
      (node (ref "R24") (pin "2") (pinfunction "2_2") (pintype "passive"))
      (node (ref "R29") (pin "2") (pinfunction "2_2") (pintype "passive"))
      (node (ref "R30") (pin "1") (pinfunction "1_1") (pintype "passive"))
      (node (ref "R31") (pin "1") (pinfunction "1_1") (pintype "passive"))
      (node (ref "R32") (pin "1") (pinfunction "1_1") (pintype "passive"))
      (node (ref "R35") (pin "1") (pinfunction "1_1") (pintype "passive"))
      (node (ref "R36") (pin "1") (pinfunction "1_1") (pintype "passive"))
      (node (ref "R37") (pin "1") (pinfunction "1_1") (pintype "passive"))
      (node (ref "R38") (pin "1") (pinfunction "1_1") (pintype "passive"))
      (node (ref "R39") (pin "1") (pinfunction "1_1") (pintype "passive"))
      (node (ref "R40") (pin "2") (pinfunction "2_2") (pintype "passive"))
      (node (ref "R43") (pin "2") (pinfunction "2_2") (pintype "passive"))
      (node (ref "R48") (pin "2") (pinfunction "2_2") (pintype "passive"))
      (node (ref "R51") (pin "2") (pinfunction "2_2") (pintype "passive"))
      (node (ref "R74_") (pin "2") (pinfunction "2_2") (pintype "passive"))
      (node (ref "U$1") (pin "3A") (pinfunction "EDGE_3A") (pintype "bidirectional"))
    )
    (net (code "2") (name "+12V") (class "Default")
      (node (ref "C43") (pin "2") (pinfunction "2_2") (pintype "passive"))
      (node (ref "C53") (pin "+") (pinfunction "+_+") (pintype "passive"))
      (node (ref "D24") (pin "C") (pinfunction "K_C") (pintype "bidirectional"))
      (node (ref "IC11") (pin "5") (pinfunction "+12V_5") (pintype "power_in"))
      (node (ref "IC12") (pin "14") (pinfunction "RFVCC_14") (pintype "power_in"))
      (node (ref "IC12") (pin "16") (pinfunction "CRVCC_16") (pintype "power_in"))
      (node (ref "L1") (pin "2") (pinfunction "A_2") (pintype "passive"))
      (node (ref "R54") (pin "1") (pinfunction "1_1") (pintype "passive"))
      (node (ref "R57") (pin "1") (pinfunction "1_1") (pintype "passive"))
      (node (ref "R58") (pin "1") (pinfunction "1_1") (pintype "passive"))
      (node (ref "R59") (pin "1") (pinfunction "1_1") (pintype "passive"))
      (node (ref "R68") (pin "1") (pinfunction "1_1") (pintype "passive"))
      (node (ref "U$1") (pin "22B") (pinfunction "EDGE_22B") (pintype "bidirectional"))
    )
    (net (code "3") (name "-5V") (class "Default")
      (node (ref "C26") (pin "1") (pinfunction "1_1") (pintype "passive"))
      (node (ref "C27") (pin "1") (pinfunction "1_1") (pintype "passive"))
      (node (ref "C50") (pin "1") (pinfunction "1_1") (pintype "passive"))
      (node (ref "D21") (pin "A") (pinfunction "A_A") (pintype "bidirectional"))
      (node (ref "IC13") (pin "1") (pinfunction "VBB_1") (pintype "input"))
      (node (ref "IC14") (pin "1") (pinfunction "VBB_1") (pintype "input"))
      (node (ref "IC15") (pin "1") (pinfunction "VBB_1") (pintype "input"))
      (node (ref "IC16") (pin "1") (pinfunction "VBB_1") (pintype "input"))
      (node (ref "IC17") (pin "1") (pinfunction "VBB_1") (pintype "input"))
      (node (ref "IC18") (pin "1") (pinfunction "VBB_1") (pintype "input"))
      (node (ref "IC19") (pin "1") (pinfunction "VBB_1") (pintype "input"))
      (node (ref "IC20") (pin "1") (pinfunction "VBB_1") (pintype "input"))
      (node (ref "R67") (pin "1") (pinfunction "1_1") (pintype "passive"))
      (node (ref "U$1") (pin "20B") (pinfunction "EDGE_20B") (pintype "bidirectional"))
    )
    (net (code "4") (name "/+12V_UNREG") (class "Default")
      (node (ref "C48") (pin "1") (pinfunction "1_1") (pintype "passive"))
      (node (ref "C51") (pin "1") (pinfunction "1_1") (pintype "passive"))
      (node (ref "Q5") (pin "E") (pinfunction "E_E") (pintype "passive"))
      (node (ref "Q6") (pin "E") (pinfunction "E_E") (pintype "passive"))
      (node (ref "U$1") (pin "23B") (pinfunction "EDGE_23B") (pintype "bidirectional"))
    )
    (net (code "5") (name "/A0") (class "Default")
      (node (ref "IC1") (pin "30") (pinfunction "A0_30") (pintype "output"))
      (node (ref "IC2") (pin "10") (pinfunction "A0_10") (pintype "input"))
      (node (ref "IC7") (pin "3") (pinfunction "1B_3") (pintype "input"))
      (node (ref "IC8") (pin "3") (pinfunction "1B_3") (pintype "input"))
      (node (ref "Q1") (pin "2") (pinfunction "B_2") (pintype "passive"))
      (node (ref "U$1") (pin "9A") (pinfunction "EDGE_9A") (pintype "bidirectional"))
    )
    (net (code "6") (name "/A1") (class "Default")
      (node (ref "IC1") (pin "31") (pinfunction "A1_31") (pintype "output"))
      (node (ref "IC2") (pin "9") (pinfunction "A1_9") (pintype "input"))
      (node (ref "IC7") (pin "6") (pinfunction "2B_6") (pintype "input"))
      (node (ref "IC8") (pin "6") (pinfunction "2B_6") (pintype "input"))
      (node (ref "U$1") (pin "10A") (pinfunction "EDGE_10A") (pintype "bidirectional"))
    )
    (net (code "7") (name "/A2") (class "Default")
      (node (ref "IC1") (pin "32") (pinfunction "A2_32") (pintype "output"))
      (node (ref "IC2") (pin "8") (pinfunction "A2_8") (pintype "input"))
      (node (ref "IC7") (pin "13") (pinfunction "4B_13") (pintype "input"))
      (node (ref "IC8") (pin "13") (pinfunction "4B_13") (pintype "input"))
      (node (ref "U$1") (pin "11A") (pinfunction "EDGE_11A") (pintype "bidirectional"))
    )
    (net (code "8") (name "/A3") (class "Default")
      (node (ref "IC1") (pin "33") (pinfunction "A3_33") (pintype "output"))
      (node (ref "IC2") (pin "7") (pinfunction "A3_7") (pintype "input"))
      (node (ref "IC7") (pin "10") (pinfunction "3B_10") (pintype "input"))
      (node (ref "IC8") (pin "10") (pinfunction "3B_10") (pintype "input"))
      (node (ref "U$1") (pin "12A") (pinfunction "EDGE_12A") (pintype "bidirectional"))
    )
    (net (code "9") (name "/A4") (class "Default")
      (node (ref "IC1") (pin "34") (pinfunction "A4_34") (pintype "output"))
      (node (ref "IC2") (pin "6") (pinfunction "A4_6") (pintype "input"))
      (node (ref "IC6") (pin "6") (pinfunction "2B_6") (pintype "input"))
      (node (ref "IC9") (pin "6") (pinfunction "2B_6") (pintype "input"))
      (node (ref "U$1") (pin "24A") (pinfunction "EDGE_24A") (pintype "bidirectional"))
    )
    (net (code "10") (name "/A5") (class "Default")
      (node (ref "IC1") (pin "35") (pinfunction "A5_35") (pintype "output"))
      (node (ref "IC2") (pin "5") (pinfunction "A5_5") (pintype "input"))
      (node (ref "IC6") (pin "13") (pinfunction "4B_13") (pintype "input"))
      (node (ref "IC9") (pin "13") (pinfunction "4B_13") (pintype "input"))
      (node (ref "U$1") (pin "23A") (pinfunction "EDGE_23A") (pintype "bidirectional"))
    )
    (net (code "11") (name "/A6") (class "Default")
      (node (ref "IC1") (pin "36") (pinfunction "A6_36") (pintype "output"))
      (node (ref "IC2") (pin "4") (pinfunction "A6_4") (pintype "input"))
      (node (ref "IC21") (pin "14") (pinfunction "A0_14") (pintype "input"))
      (node (ref "IC22") (pin "14") (pinfunction "A0_14") (pintype "input"))
      (node (ref "IC23") (pin "14") (pinfunction "A0_14") (pintype "input"))
      (node (ref "IC24") (pin "14") (pinfunction "A0_14") (pintype "input"))
      (node (ref "IC5") (pin "12") (pinfunction "D_12") (pintype "input"))
      (node (ref "IC9") (pin "10") (pinfunction "3B_10") (pintype "input"))
      (node (ref "U$1") (pin "22A") (pinfunction "EDGE_22A") (pintype "bidirectional"))
    )
    (net (code "12") (name "/A7") (class "Default")
      (node (ref "IC1") (pin "37") (pinfunction "A7_37") (pintype "output"))
      (node (ref "IC2") (pin "3") (pinfunction "A7_3") (pintype "input"))
      (node (ref "IC26") (pin "12") (pinfunction "I0_12") (pintype "input"))
      (node (ref "IC8") (pin "2") (pinfunction "1A_2") (pintype "input"))
      (node (ref "U$1") (pin "21A") (pinfunction "EDGE_21A") (pintype "bidirectional"))
    )
    (net (code "13") (name "/A7'") (class "Default")
      (node (ref "IC21") (pin "10") (pinfunction "A7_10") (pintype "input"))
      (node (ref "IC22") (pin "10") (pinfunction "A7_10") (pintype "input"))
      (node (ref "IC23") (pin "10") (pinfunction "A7_10") (pintype "input"))
      (node (ref "IC24") (pin "10") (pinfunction "A7_10") (pintype "input"))
      (node (ref "IC26") (pin "8") (pinfunction "O_8") (pintype "output"))
    )
    (net (code "14") (name "/A8") (class "Default")
      (node (ref "D2") (pin "C") (pinfunction "K_C") (pintype "bidirectional"))
      (node (ref "IC1") (pin "38") (pinfunction "A8_38") (pintype "output"))
      (node (ref "IC2") (pin "25") (pinfunction "A8_25") (pintype "input"))
      (node (ref "IC7") (pin "5") (pinfunction "2A_5") (pintype "input"))
      (node (ref "IC8") (pin "5") (pinfunction "2A_5") (pintype "input"))
      (node (ref "U$1") (pin "26B") (pinfunction "EDGE_26B") (pintype "bidirectional"))
    )
    (net (code "15") (name "/A8-1") (class "Default")
      (node (ref "IC21") (pin "7") (pinfunction "A5_7") (pintype "input"))
      (node (ref "IC22") (pin "7") (pinfunction "A5_7") (pintype "input"))
      (node (ref "IC23") (pin "7") (pinfunction "A5_7") (pintype "input"))
      (node (ref "IC24") (pin "7") (pinfunction "A5_7") (pintype "input"))
      (node (ref "IC7") (pin "7") (pinfunction "2Y_7") (pintype "output"))
    )
    (net (code "16") (name "/A9") (class "Default")
      (node (ref "D3") (pin "C") (pinfunction "K_C") (pintype "bidirectional"))
      (node (ref "IC1") (pin "39") (pinfunction "A9_39") (pintype "output"))
      (node (ref "IC2") (pin "24") (pinfunction "A9_24") (pintype "input"))
      (node (ref "IC7") (pin "14") (pinfunction "4A_14") (pintype "input"))
      (node (ref "IC8") (pin "14") (pinfunction "4A_14") (pintype "input"))
      (node (ref "U$1") (pin "27A") (pinfunction "EDGE_27A") (pintype "bidirectional"))
    )
    (net (code "17") (name "/A9-2") (class "Default")
      (node (ref "IC21") (pin "8") (pinfunction "A4_8") (pintype "input"))
      (node (ref "IC22") (pin "8") (pinfunction "A4_8") (pintype "input"))
      (node (ref "IC23") (pin "8") (pinfunction "A4_8") (pintype "input"))
      (node (ref "IC24") (pin "8") (pinfunction "A4_8") (pintype "input"))
      (node (ref "IC7") (pin "12") (pinfunction "4Y_12") (pintype "output"))
    )
    (net (code "18") (name "/A10") (class "Default")
      (node (ref "D4") (pin "C") (pinfunction "K_C") (pintype "bidirectional"))
      (node (ref "IC1") (pin "40") (pinfunction "A10_40") (pintype "output"))
      (node (ref "IC2") (pin "21") (pinfunction "A10_21") (pintype "input"))
      (node (ref "IC7") (pin "11") (pinfunction "3A_11") (pintype "input"))
      (node (ref "IC8") (pin "11") (pinfunction "3A_11") (pintype "input"))
      (node (ref "U$1") (pin "27B") (pinfunction "EDGE_27B") (pintype "bidirectional"))
    )
    (net (code "19") (name "/A10-3") (class "Default")
      (node (ref "IC21") (pin "11") (pinfunction "A3_11") (pintype "input"))
      (node (ref "IC22") (pin "11") (pinfunction "A3_11") (pintype "input"))
      (node (ref "IC23") (pin "11") (pinfunction "A3_11") (pintype "input"))
      (node (ref "IC24") (pin "11") (pinfunction "A3_11") (pintype "input"))
      (node (ref "IC7") (pin "9") (pinfunction "3Y_9") (pintype "output"))
    )
    (net (code "20") (name "/A11") (class "Default")
      (node (ref "D5") (pin "C") (pinfunction "K_C") (pintype "bidirectional"))
      (node (ref "IC1") (pin "1") (pinfunction "A11_1") (pintype "output"))
      (node (ref "IC2") (pin "23") (pinfunction "A11_23") (pintype "input"))
      (node (ref "IC6") (pin "5") (pinfunction "2A_5") (pintype "input"))
      (node (ref "IC9") (pin "5") (pinfunction "2A_5") (pintype "input"))
      (node (ref "U$1") (pin "28A") (pinfunction "EDGE_28A") (pintype "bidirectional"))
    )
    (net (code "21") (name "/A11-4") (class "Default")
      (node (ref "IC21") (pin "12") (pinfunction "A2_12") (pintype "input"))
      (node (ref "IC22") (pin "12") (pinfunction "A2_12") (pintype "input"))
      (node (ref "IC23") (pin "12") (pinfunction "A2_12") (pintype "input"))
      (node (ref "IC24") (pin "12") (pinfunction "A2_12") (pintype "input"))
      (node (ref "IC6") (pin "7") (pinfunction "2Y_7") (pintype "output"))
    )
    (net (code "22") (name "/A12") (class "Default")
      (node (ref "D6") (pin "C") (pinfunction "K_C") (pintype "bidirectional"))
      (node (ref "IC1") (pin "2") (pinfunction "A12_2") (pintype "output"))
      (node (ref "IC2") (pin "2") (pinfunction "A12_2") (pintype "input"))
      (node (ref "IC6") (pin "14") (pinfunction "4A_14") (pintype "input"))
      (node (ref "IC9") (pin "14") (pinfunction "4A_14") (pintype "input"))
      (node (ref "U$1") (pin "2A") (pinfunction "EDGE_2A") (pintype "bidirectional"))
    )
    (net (code "23") (name "/A12-5") (class "Default")
      (node (ref "IC21") (pin "13") (pinfunction "A1_13") (pintype "input"))
      (node (ref "IC22") (pin "13") (pinfunction "A1_13") (pintype "input"))
      (node (ref "IC23") (pin "13") (pinfunction "A1_13") (pintype "input"))
      (node (ref "IC24") (pin "13") (pinfunction "A1_13") (pintype "input"))
      (node (ref "IC6") (pin "12") (pinfunction "4Y_12") (pintype "output"))
    )
    (net (code "24") (name "/A13") (class "Default")
      (node (ref "D7") (pin "C") (pinfunction "K_C") (pintype "bidirectional"))
      (node (ref "IC1") (pin "3") (pinfunction "A13_3") (pintype "output"))
      (node (ref "IC2") (pin "26") (pinfunction "A13_26") (pintype "input"))
      (node (ref "IC7") (pin "2") (pinfunction "1A_2") (pintype "input"))
      (node (ref "IC9") (pin "11") (pinfunction "3A_11") (pintype "input"))
      (node (ref "U$1") (pin "2B") (pinfunction "EDGE_2B") (pintype "bidirectional"))
    )
    (net (code "25") (name "/A13-0") (class "Default")
      (node (ref "IC21") (pin "6") (pinfunction "A6_6") (pintype "input"))
      (node (ref "IC22") (pin "6") (pinfunction "A6_6") (pintype "input"))
      (node (ref "IC23") (pin "6") (pinfunction "A6_6") (pintype "input"))
      (node (ref "IC24") (pin "6") (pinfunction "A6_6") (pintype "input"))
      (node (ref "IC7") (pin "4") (pinfunction "1Y_4") (pintype "output"))
    )
    (net (code "26") (name "/A14") (class "Default")
      (node (ref "D12") (pin "A") (pinfunction "A_A") (pintype "bidirectional"))
      (node (ref "D8") (pin "C") (pinfunction "K_C") (pintype "bidirectional"))
      (node (ref "IC1") (pin "4") (pinfunction "A14_4") (pintype "output"))
      (node (ref "IC25") (pin "4") (pinfunction "I0_4") (pintype "input"))
      (node (ref "IC27") (pin "12") (pinfunction "I0_12") (pintype "input"))
      (node (ref "IC28") (pin "1") (pinfunction "I_1") (pintype "input"))
      (node (ref "IC3") (pin "37") (pinfunction "A14_37") (pintype "input"))
      (node (ref "U$1") (pin "1A") (pinfunction "EDGE_1A") (pintype "bidirectional"))
    )
    (net (code "27") (name "/A15") (class "Default")
      (node (ref "D11") (pin "A") (pinfunction "A_A") (pintype "bidirectional"))
      (node (ref "D9") (pin "C") (pinfunction "K_C") (pintype "bidirectional"))
      (node (ref "IC1") (pin "5") (pinfunction "A15_5") (pintype "output"))
      (node (ref "IC25") (pin "13") (pinfunction "I1_13") (pintype "input"))
      (node (ref "IC27") (pin "13") (pinfunction "I1_13") (pintype "input"))
      (node (ref "IC3") (pin "38") (pinfunction "A15_38") (pintype "input"))
      (node (ref "U$1") (pin "1B") (pinfunction "EDGE_1B") (pintype "bidirectional"))
    )
    (net (code "28") (name "/AA0") (class "Default")
      (node (ref "IC13") (pin "5") (pinfunction "A0_5") (pintype "input"))
      (node (ref "IC14") (pin "5") (pinfunction "A0_5") (pintype "input"))
      (node (ref "IC15") (pin "5") (pinfunction "A0_5") (pintype "input"))
      (node (ref "IC16") (pin "5") (pinfunction "A0_5") (pintype "input"))
      (node (ref "IC17") (pin "5") (pinfunction "A0_5") (pintype "input"))
      (node (ref "IC18") (pin "5") (pinfunction "A0_5") (pintype "input"))
      (node (ref "IC19") (pin "5") (pinfunction "A0_5") (pintype "input"))
      (node (ref "IC20") (pin "5") (pinfunction "A0_5") (pintype "input"))
      (node (ref "IC3") (pin "9") (pinfunction "A0_9") (pintype "output"))
      (node (ref "R9") (pin "1") (pinfunction "1_1") (pintype "passive"))
    )
    (net (code "29") (name "/AA1") (class "Default")
      (node (ref "IC13") (pin "7") (pinfunction "A1_7") (pintype "input"))
      (node (ref "IC14") (pin "7") (pinfunction "A1_7") (pintype "input"))
      (node (ref "IC15") (pin "7") (pinfunction "A1_7") (pintype "input"))
      (node (ref "IC16") (pin "7") (pinfunction "A1_7") (pintype "input"))
      (node (ref "IC17") (pin "7") (pinfunction "A1_7") (pintype "input"))
      (node (ref "IC18") (pin "7") (pinfunction "A1_7") (pintype "input"))
      (node (ref "IC19") (pin "7") (pinfunction "A1_7") (pintype "input"))
      (node (ref "IC20") (pin "7") (pinfunction "A1_7") (pintype "input"))
      (node (ref "IC3") (pin "7") (pinfunction "A1_7") (pintype "output"))
      (node (ref "R11") (pin "1") (pinfunction "1_1") (pintype "passive"))
    )
    (net (code "30") (name "/AA2") (class "Default")
      (node (ref "IC13") (pin "6") (pinfunction "A2_6") (pintype "input"))
      (node (ref "IC14") (pin "6") (pinfunction "A2_6") (pintype "input"))
      (node (ref "IC15") (pin "6") (pinfunction "A2_6") (pintype "input"))
      (node (ref "IC16") (pin "6") (pinfunction "A2_6") (pintype "input"))
      (node (ref "IC17") (pin "6") (pinfunction "A2_6") (pintype "input"))
      (node (ref "IC18") (pin "6") (pinfunction "A2_6") (pintype "input"))
      (node (ref "IC19") (pin "6") (pinfunction "A2_6") (pintype "input"))
      (node (ref "IC20") (pin "6") (pinfunction "A2_6") (pintype "input"))
      (node (ref "IC3") (pin "8") (pinfunction "A2_8") (pintype "output"))
      (node (ref "R10") (pin "1") (pinfunction "1_1") (pintype "passive"))
    )
    (net (code "31") (name "/AA3") (class "Default")
      (node (ref "IC13") (pin "12") (pinfunction "A3_12") (pintype "input"))
      (node (ref "IC14") (pin "12") (pinfunction "A3_12") (pintype "input"))
      (node (ref "IC15") (pin "12") (pinfunction "A3_12") (pintype "input"))
      (node (ref "IC16") (pin "12") (pinfunction "A3_12") (pintype "input"))
      (node (ref "IC17") (pin "12") (pinfunction "A3_12") (pintype "input"))
      (node (ref "IC18") (pin "12") (pinfunction "A3_12") (pintype "input"))
      (node (ref "IC19") (pin "12") (pinfunction "A3_12") (pintype "input"))
      (node (ref "IC20") (pin "12") (pinfunction "A3_12") (pintype "input"))
      (node (ref "IC3") (pin "4") (pinfunction "A3_4") (pintype "output"))
      (node (ref "R14") (pin "1") (pinfunction "1_1") (pintype "passive"))
    )
    (net (code "32") (name "/AA4") (class "Default")
      (node (ref "IC13") (pin "11") (pinfunction "A4_11") (pintype "input"))
      (node (ref "IC14") (pin "11") (pinfunction "A4_11") (pintype "input"))
      (node (ref "IC15") (pin "11") (pinfunction "A4_11") (pintype "input"))
      (node (ref "IC16") (pin "11") (pinfunction "A4_11") (pintype "input"))
      (node (ref "IC17") (pin "11") (pinfunction "A4_11") (pintype "input"))
      (node (ref "IC18") (pin "11") (pinfunction "A4_11") (pintype "input"))
      (node (ref "IC19") (pin "11") (pinfunction "A4_11") (pintype "input"))
      (node (ref "IC20") (pin "11") (pinfunction "A4_11") (pintype "input"))
      (node (ref "IC3") (pin "5") (pinfunction "A4_5") (pintype "output"))
      (node (ref "R13") (pin "1") (pinfunction "1_1") (pintype "passive"))
    )
    (net (code "33") (name "/AA5") (class "Default")
      (node (ref "IC13") (pin "10") (pinfunction "A5_10") (pintype "input"))
      (node (ref "IC14") (pin "10") (pinfunction "A5_10") (pintype "input"))
      (node (ref "IC15") (pin "10") (pinfunction "A5_10") (pintype "input"))
      (node (ref "IC16") (pin "10") (pinfunction "A5_10") (pintype "input"))
      (node (ref "IC17") (pin "10") (pinfunction "A5_10") (pintype "input"))
      (node (ref "IC18") (pin "10") (pinfunction "A5_10") (pintype "input"))
      (node (ref "IC19") (pin "10") (pinfunction "A5_10") (pintype "input"))
      (node (ref "IC20") (pin "10") (pinfunction "A5_10") (pintype "input"))
      (node (ref "IC3") (pin "6") (pinfunction "A5_6") (pintype "output"))
      (node (ref "R12") (pin "1") (pinfunction "1_1") (pintype "passive"))
    )
    (net (code "34") (name "/AA6") (class "Default")
      (node (ref "IC13") (pin "13") (pinfunction "A6_13") (pintype "input"))
      (node (ref "IC14") (pin "13") (pinfunction "A6_13") (pintype "input"))
      (node (ref "IC15") (pin "13") (pinfunction "A6_13") (pintype "input"))
      (node (ref "IC16") (pin "13") (pinfunction "A6_13") (pintype "input"))
      (node (ref "IC17") (pin "13") (pinfunction "A6_13") (pintype "input"))
      (node (ref "IC18") (pin "13") (pinfunction "A6_13") (pintype "input"))
      (node (ref "IC19") (pin "13") (pinfunction "A6_13") (pintype "input"))
      (node (ref "IC20") (pin "13") (pinfunction "A6_13") (pintype "input"))
      (node (ref "IC3") (pin "3") (pinfunction "A6_3") (pintype "output"))
      (node (ref "R15") (pin "1") (pinfunction "1_1") (pintype "passive"))
    )
    (net (code "35") (name "/CARRIER") (class "Default")
      (node (ref "C47") (pin "1") (pinfunction "1_1") (pintype "passive"))
      (node (ref "D17") (pin "A") (pinfunction "A_A") (pintype "bidirectional"))
      (node (ref "D18") (pin "C") (pinfunction "K_C") (pintype "bidirectional"))
      (node (ref "IC3") (pin "39") (pinfunction "CARRIER_39") (pintype "output"))
      (node (ref "R64") (pin "2") (pinfunction "2_2") (pintype "passive"))
      (node (ref "R71") (pin "2") (pinfunction "2_2") (pintype "passive"))
    )
    (net (code "36") (name "/CLK") (class "Default")
      (node (ref "C9") (pin "2") (pinfunction "2_2") (pintype "passive"))
      (node (ref "IC3") (pin "36") (pinfunction "CKOUT_36") (pintype "output"))
      (node (ref "R49") (pin "2") (pinfunction "2_2") (pintype "passive"))
      (node (ref "R51") (pin "1") (pinfunction "1_1") (pintype "passive"))
      (node (ref "U$1") (pin "8A") (pinfunction "EDGE_8A") (pintype "bidirectional"))
    )
    (net (code "37") (name "/D0") (class "Default")
      (node (ref "IC1") (pin "14") (pinfunction "D0_14") (pintype "bidirectional"))
      (node (ref "IC10") (pin "3") (pinfunction "Y1_3") (pintype "tri_state"))
      (node (ref "IC2") (pin "11") (pinfunction "O0_11") (pintype "tri_state"))
      (node (ref "IC21") (pin "2") (pinfunction "I/O1_2") (pintype "bidirectional"))
      (node (ref "IC23") (pin "2") (pinfunction "I/O1_2") (pintype "bidirectional"))
      (node (ref "R1") (pin "2") (pinfunction "2_2") (pintype "passive"))
      (node (ref "R17") (pin "1") (pinfunction "1_1") (pintype "passive"))
      (node (ref "U$1") (pin "6B") (pinfunction "EDGE_6B") (pintype "bidirectional"))
    )
    (net (code "38") (name "/D0'") (class "Default")
      (node (ref "IC20") (pin "14") (pinfunction "DO_14") (pintype "bidirectional"))
      (node (ref "IC20") (pin "2") (pinfunction "DI_2") (pintype "bidirectional"))
      (node (ref "IC3") (pin "25") (pinfunction "D0_25") (pintype "bidirectional"))
      (node (ref "R1") (pin "1") (pinfunction "1_1") (pintype "passive"))
    )
    (net (code "39") (name "/D1") (class "Default")
      (node (ref "IC1") (pin "15") (pinfunction "D1_15") (pintype "bidirectional"))
      (node (ref "IC10") (pin "5") (pinfunction "Y2_5") (pintype "tri_state"))
      (node (ref "IC2") (pin "12") (pinfunction "O1_12") (pintype "tri_state"))
      (node (ref "IC21") (pin "3") (pinfunction "I/O2_3") (pintype "bidirectional"))
      (node (ref "IC23") (pin "3") (pinfunction "I/O2_3") (pintype "bidirectional"))
      (node (ref "R18") (pin "1") (pinfunction "1_1") (pintype "passive"))
      (node (ref "R2") (pin "2") (pinfunction "2_2") (pintype "passive"))
      (node (ref "U$1") (pin "7B") (pinfunction "EDGE_7B") (pintype "bidirectional"))
    )
    (net (code "40") (name "/D1'") (class "Default")
      (node (ref "IC19") (pin "14") (pinfunction "DO_14") (pintype "bidirectional"))
      (node (ref "IC19") (pin "2") (pinfunction "DI_2") (pintype "bidirectional"))
      (node (ref "IC3") (pin "26") (pinfunction "D1_26") (pintype "bidirectional"))
      (node (ref "R2") (pin "1") (pinfunction "1_1") (pintype "passive"))
    )
    (net (code "41") (name "/D2") (class "Default")
      (node (ref "IC1") (pin "12") (pinfunction "D2_12") (pintype "bidirectional"))
      (node (ref "IC10") (pin "7") (pinfunction "Y3_7") (pintype "tri_state"))
      (node (ref "IC2") (pin "13") (pinfunction "O2_13") (pintype "tri_state"))
      (node (ref "IC21") (pin "15") (pinfunction "I/O3_15") (pintype "bidirectional"))
      (node (ref "IC23") (pin "15") (pinfunction "I/O3_15") (pintype "bidirectional"))
      (node (ref "R19") (pin "1") (pinfunction "1_1") (pintype "passive"))
      (node (ref "R3") (pin "2") (pinfunction "2_2") (pintype "passive"))
      (node (ref "U$1") (pin "8B") (pinfunction "EDGE_8B") (pintype "bidirectional"))
    )
    (net (code "42") (name "/D2'") (class "Default")
      (node (ref "IC18") (pin "14") (pinfunction "DO_14") (pintype "bidirectional"))
      (node (ref "IC18") (pin "2") (pinfunction "DI_2") (pintype "bidirectional"))
      (node (ref "IC3") (pin "27") (pinfunction "D2_27") (pintype "bidirectional"))
      (node (ref "R3") (pin "1") (pinfunction "1_1") (pintype "passive"))
    )
    (net (code "43") (name "/D3") (class "Default")
      (node (ref "IC1") (pin "8") (pinfunction "D3_8") (pintype "bidirectional"))
      (node (ref "IC10") (pin "9") (pinfunction "Y4_9") (pintype "tri_state"))
      (node (ref "IC2") (pin "15") (pinfunction "O3_15") (pintype "tri_state"))
      (node (ref "IC21") (pin "17") (pinfunction "I/O4_17") (pintype "bidirectional"))
      (node (ref "IC23") (pin "17") (pinfunction "I/O4_17") (pintype "bidirectional"))
      (node (ref "R20") (pin "1") (pinfunction "1_1") (pintype "passive"))
      (node (ref "R4") (pin "2") (pinfunction "2_2") (pintype "passive"))
      (node (ref "U$1") (pin "11B") (pinfunction "EDGE_11B") (pintype "bidirectional"))
    )
    (net (code "44") (name "/D3'") (class "Default")
      (node (ref "IC17") (pin "14") (pinfunction "DO_14") (pintype "bidirectional"))
      (node (ref "IC17") (pin "2") (pinfunction "DI_2") (pintype "bidirectional"))
      (node (ref "IC3") (pin "28") (pinfunction "D3_28") (pintype "bidirectional"))
      (node (ref "R4") (pin "1") (pinfunction "1_1") (pintype "passive"))
    )
    (net (code "45") (name "/D4") (class "Default")
      (node (ref "IC1") (pin "7") (pinfunction "D4_7") (pintype "bidirectional"))
      (node (ref "IC10") (pin "11") (pinfunction "Y5_11") (pintype "tri_state"))
      (node (ref "IC2") (pin "16") (pinfunction "O4_16") (pintype "tri_state"))
      (node (ref "IC22") (pin "2") (pinfunction "I/O1_2") (pintype "bidirectional"))
      (node (ref "IC24") (pin "2") (pinfunction "I/O1_2") (pintype "bidirectional"))
      (node (ref "R21") (pin "1") (pinfunction "1_1") (pintype "passive"))
      (node (ref "R5") (pin "2") (pinfunction "2_2") (pintype "passive"))
      (node (ref "U$1") (pin "12B") (pinfunction "EDGE_12B") (pintype "bidirectional"))
    )
    (net (code "46") (name "/D4'") (class "Default")
      (node (ref "IC16") (pin "14") (pinfunction "DO_14") (pintype "bidirectional"))
      (node (ref "IC16") (pin "2") (pinfunction "DI_2") (pintype "bidirectional"))
      (node (ref "IC3") (pin "29") (pinfunction "D4_29") (pintype "bidirectional"))
      (node (ref "R5") (pin "1") (pinfunction "1_1") (pintype "passive"))
    )
    (net (code "47") (name "/D5") (class "Default")
      (node (ref "IC1") (pin "9") (pinfunction "D5_9") (pintype "bidirectional"))
      (node (ref "IC2") (pin "17") (pinfunction "O5_17") (pintype "tri_state"))
      (node (ref "IC22") (pin "3") (pinfunction "I/O2_3") (pintype "bidirectional"))
      (node (ref "IC24") (pin "3") (pinfunction "I/O2_3") (pintype "bidirectional"))
      (node (ref "R22") (pin "1") (pinfunction "1_1") (pintype "passive"))
      (node (ref "R6") (pin "2") (pinfunction "2_2") (pintype "passive"))
      (node (ref "U$1") (pin "10B") (pinfunction "EDGE_10B") (pintype "bidirectional"))
    )
    (net (code "48") (name "/D5'") (class "Default")
      (node (ref "IC15") (pin "14") (pinfunction "DO_14") (pintype "bidirectional"))
      (node (ref "IC15") (pin "2") (pinfunction "DI_2") (pintype "bidirectional"))
      (node (ref "IC3") (pin "30") (pinfunction "D5_30") (pintype "bidirectional"))
      (node (ref "R6") (pin "1") (pinfunction "1_1") (pintype "passive"))
    )
    (net (code "49") (name "/D6") (class "Default")
      (node (ref "IC1") (pin "10") (pinfunction "D6_10") (pintype "bidirectional"))
      (node (ref "IC10") (pin "13") (pinfunction "Y6_13") (pintype "tri_state"))
      (node (ref "IC2") (pin "18") (pinfunction "O6_18") (pintype "tri_state"))
      (node (ref "IC22") (pin "15") (pinfunction "I/O3_15") (pintype "bidirectional"))
      (node (ref "IC24") (pin "15") (pinfunction "I/O3_15") (pintype "bidirectional"))
      (node (ref "R23") (pin "1") (pinfunction "1_1") (pintype "passive"))
      (node (ref "R7") (pin "2") (pinfunction "2_2") (pintype "passive"))
      (node (ref "U$1") (pin "9B") (pinfunction "EDGE_9B") (pintype "bidirectional"))
    )
    (net (code "50") (name "/D6'") (class "Default")
      (node (ref "IC14") (pin "14") (pinfunction "DO_14") (pintype "bidirectional"))
      (node (ref "IC14") (pin "2") (pinfunction "DI_2") (pintype "bidirectional"))
      (node (ref "IC3") (pin "31") (pinfunction "D6_31") (pintype "bidirectional"))
      (node (ref "R7") (pin "1") (pinfunction "1_1") (pintype "passive"))
    )
    (net (code "51") (name "/D7") (class "Default")
      (node (ref "D1") (pin "A") (pinfunction "A_A") (pintype "bidirectional"))
      (node (ref "IC1") (pin "13") (pinfunction "D7_13") (pintype "bidirectional"))
      (node (ref "IC2") (pin "19") (pinfunction "O7_19") (pintype "tri_state"))
      (node (ref "IC22") (pin "17") (pinfunction "I/O4_17") (pintype "bidirectional"))
      (node (ref "IC24") (pin "17") (pinfunction "I/O4_17") (pintype "bidirectional"))
      (node (ref "R24") (pin "1") (pinfunction "1_1") (pintype "passive"))
      (node (ref "R8") (pin "2") (pinfunction "2_2") (pintype "passive"))
      (node (ref "U$1") (pin "3B") (pinfunction "EDGE_3B") (pintype "bidirectional"))
    )
    (net (code "52") (name "/D7'") (class "Default")
      (node (ref "IC13") (pin "14") (pinfunction "DO_14") (pintype "bidirectional"))
      (node (ref "IC13") (pin "2") (pinfunction "DI_2") (pintype "bidirectional"))
      (node (ref "IC3") (pin "32") (pinfunction "D7_32") (pintype "bidirectional"))
      (node (ref "R8") (pin "1") (pinfunction "1_1") (pintype "passive"))
    )
    (net (code "53") (name "/MREQ'") (class "Default")
      (node (ref "D10") (pin "C") (pinfunction "K_C") (pintype "bidirectional"))
      (node (ref "IC3") (pin "15") (pinfunction "~{MREQ}_15") (pintype "input"))
      (node (ref "R34") (pin "2") (pinfunction "2_2") (pintype "passive"))
    )
    (net (code "54") (name "/RESET") (class "Default")
      (node (ref "D10") (pin "A") (pinfunction "A_A") (pintype "bidirectional"))
      (node (ref "IC28") (pin "12") (pinfunction "O_12") (pintype "output"))
    )
    (net (code "55") (name "/SNDIN") (class "Default")
      (node (ref "C54") (pin "1") (pinfunction "1_1") (pintype "passive"))
      (node (ref "C57") (pin "1") (pinfunction "1_1") (pintype "passive"))
      (node (ref "D13") (pin "A") (pinfunction "A_A") (pintype "bidirectional"))
      (node (ref "D14") (pin "C") (pinfunction "C_C") (pintype "passive"))
      (node (ref "Q7") (pin "2") (pinfunction "B_2") (pintype "passive"))
      (node (ref "R40") (pin "1") (pinfunction "1_1") (pintype "passive"))
      (node (ref "R41") (pin "2") (pinfunction "2_2") (pintype "passive"))
      (node (ref "R42") (pin "2") (pinfunction "2_2") (pintype "passive"))
      (node (ref "TP3") (pin "1") (pinfunction "TP_1") (pintype "input"))
    )
    (net (code "56") (name "/{slash}INT") (class "Default")
      (node (ref "IC1") (pin "16") (pinfunction "~{INT}_16") (pintype "input"))
      (node (ref "R25") (pin "2") (pinfunction "2_2") (pintype "passive"))
      (node (ref "TP10") (pin "1") (pinfunction "TP_1") (pintype "input"))
      (node (ref "U$1") (pin "13B") (pinfunction "EDGE_13B") (pintype "bidirectional"))
    )
    (net (code "57") (name "/~{A}{slash}B") (class "Default")
      (node (ref "IC27") (pin "3") (pinfunction "O_3") (pintype "output"))
      (node (ref "IC6") (pin "1") (pinfunction "~{A}/B_1") (pintype "input"))
      (node (ref "IC7") (pin "1") (pinfunction "~{A}/B_1") (pintype "input"))
      (node (ref "R45") (pin "1") (pinfunction "1_1") (pintype "passive"))
    )
    (net (code "58") (name "/~{CAS0}") (class "Default")
      (node (ref "IC23") (pin "1") (pinfunction "~{OE}_1") (pintype "input"))
      (node (ref "IC23") (pin "16") (pinfunction "~{CAS}_16") (pintype "input"))
      (node (ref "IC24") (pin "1") (pinfunction "~{OE}_1") (pintype "input"))
      (node (ref "IC24") (pin "16") (pinfunction "~{CAS}_16") (pintype "input"))
      (node (ref "IC25") (pin "8") (pinfunction "O_8") (pintype "output"))
    )
    (net (code "59") (name "/~{CAS1}") (class "Default")
      (node (ref "IC21") (pin "1") (pinfunction "~{OE}_1") (pintype "input"))
      (node (ref "IC21") (pin "16") (pinfunction "~{CAS}_16") (pintype "input"))
      (node (ref "IC22") (pin "1") (pinfunction "~{OE}_1") (pintype "input"))
      (node (ref "IC22") (pin "16") (pinfunction "~{CAS}_16") (pintype "input"))
      (node (ref "IC25") (pin "6") (pinfunction "O_6") (pintype "output"))
    )
    (net (code "60") (name "/~{IORQGE}") (class "Default")
      (node (ref "IC3") (pin "2") (pinfunction "~{CS}_2") (pintype "input"))
      (node (ref "Q1") (pin "1") (pinfunction "E_1") (pintype "passive"))
      (node (ref "R27") (pin "2") (pinfunction "2_2") (pintype "passive"))
      (node (ref "U$1") (pin "13A") (pinfunction "EDGE_13A") (pintype "bidirectional"))
    )
    (net (code "61") (name "/~{IORQ}") (class "Default")
      (node (ref "IC1") (pin "20") (pinfunction "~{IORQ}_20") (pintype "output"))
      (node (ref "R27") (pin "1") (pinfunction "1_1") (pintype "passive"))
      (node (ref "U$1") (pin "17B") (pinfunction "EDGE_17B") (pintype "bidirectional"))
    )
    (net (code "62") (name "/~{KBD}") (class "Default")
      (node (ref "D1") (pin "C") (pinfunction "K_C") (pintype "bidirectional"))
      (node (ref "IC10") (pin "1") (pinfunction "G1_1") (pintype "input"))
      (node (ref "IC3") (pin "10") (pinfunction "~{KBD}_10") (pintype "output"))
    )
    (net (code "63") (name "/~{MREQ}") (class "Default")
      (node (ref "IC1") (pin "19") (pinfunction "~{MREQ}_19") (pintype "output"))
      (node (ref "IC2") (pin "22") (pinfunction "~{OE}_22") (pintype "input"))
      (node (ref "IC27") (pin "4") (pinfunction "I0_4") (pintype "input"))
      (node (ref "R34") (pin "1") (pinfunction "1_1") (pintype "passive"))
      (node (ref "U$1") (pin "16B") (pinfunction "EDGE_16B") (pintype "bidirectional"))
    )
    (net (code "64") (name "/~{RAS}") (class "Default")
      (node (ref "IC21") (pin "5") (pinfunction "~{RAS}_5") (pintype "input"))
      (node (ref "IC22") (pin "5") (pinfunction "~{RAS}_5") (pintype "input"))
      (node (ref "IC23") (pin "5") (pinfunction "~{RAS}_5") (pintype "input"))
      (node (ref "IC24") (pin "5") (pinfunction "~{RAS}_5") (pintype "input"))
      (node (ref "IC27") (pin "6") (pinfunction "O_6") (pintype "output"))
      (node (ref "IC27") (pin "9") (pinfunction "I0_9") (pintype "input"))
      (node (ref "R28") (pin "1") (pinfunction "1_1") (pintype "passive"))
    )
    (net (code "65") (name "/~{RD}") (class "Default")
      (node (ref "IC1") (pin "21") (pinfunction "~{RD}_21") (pintype "output"))
      (node (ref "IC2") (pin "27") (pinfunction "~{PGM}_27") (pintype "input"))
      (node (ref "IC25") (pin "2") (pinfunction "I1_2") (pintype "input"))
      (node (ref "IC3") (pin "17") (pinfunction "~{RD}_17") (pintype "input"))
      (node (ref "U$1") (pin "18B") (pinfunction "EDGE_18B") (pintype "bidirectional"))
    )
    (net (code "66") (name "/~{RESET}") (class "Default")
      (node (ref "C17") (pin "1") (pinfunction "1_1") (pintype "passive"))
      (node (ref "IC1") (pin "26") (pinfunction "~{RESET}_26") (pintype "input"))
      (node (ref "IC28") (pin "13") (pinfunction "I_13") (pintype "input"))
      (node (ref "R29") (pin "1") (pinfunction "1_1") (pintype "passive"))
      (node (ref "U$1") (pin "20A") (pinfunction "EDGE_20A") (pintype "bidirectional"))
    )
    (net (code "67") (name "/~{RFSH}") (class "Default")
      (node (ref "IC1") (pin "28") (pinfunction "~{RFSH}_28") (pintype "output"))
      (node (ref "IC26") (pin "13") (pinfunction "I1_13") (pintype "input"))
      (node (ref "IC26") (pin "2") (pinfunction "I1_2") (pintype "input"))
      (node (ref "IC5") (pin "11") (pinfunction "CLK_11") (pintype "input"))
      (node (ref "U$1") (pin "25B") (pinfunction "EDGE_25B") (pintype "bidirectional"))
    )
    (net (code "68") (name "/~{ROMCS}") (class "Default")
      (node (ref "IC2") (pin "20") (pinfunction "~{CE}_20") (pintype "input"))
      (node (ref "R26") (pin "2") (pinfunction "2_2") (pintype "passive"))
      (node (ref "TP9") (pin "1") (pinfunction "TP_1") (pintype "input"))
      (node (ref "U$1") (pin "25A") (pinfunction "EDGE_25A") (pintype "bidirectional"))
    )
    (net (code "69") (name "/~{ULAINT}") (class "Default")
      (node (ref "IC3") (pin "34") (pinfunction "~{INT}_34") (pintype "output"))
      (node (ref "R25") (pin "1") (pinfunction "1_1") (pintype "passive"))
    )
    (net (code "70") (name "/~{VCAS}") (class "Default")
      (node (ref "IC13") (pin "15") (pinfunction "~{CAS}_15") (pintype "input"))
      (node (ref "IC14") (pin "15") (pinfunction "~{CAS}_15") (pintype "input"))
      (node (ref "IC15") (pin "15") (pinfunction "~{CAS}_15") (pintype "input"))
      (node (ref "IC16") (pin "15") (pinfunction "~{CAS}_15") (pintype "input"))
      (node (ref "IC17") (pin "15") (pinfunction "~{CAS}_15") (pintype "input"))
      (node (ref "IC18") (pin "15") (pinfunction "~{CAS}_15") (pintype "input"))
      (node (ref "IC19") (pin "15") (pinfunction "~{CAS}_15") (pintype "input"))
      (node (ref "IC20") (pin "15") (pinfunction "~{CAS}_15") (pintype "input"))
      (node (ref "IC3") (pin "12") (pinfunction "~{VCAS}_12") (pintype "output"))
      (node (ref "TP5") (pin "1") (pinfunction "TP_1") (pintype "input"))
    )
    (net (code "71") (name "/~{VRAS}") (class "Default")
      (node (ref "IC13") (pin "4") (pinfunction "~{RAS}_4") (pintype "input"))
      (node (ref "IC14") (pin "4") (pinfunction "~{RAS}_4") (pintype "input"))
      (node (ref "IC15") (pin "4") (pinfunction "~{RAS}_4") (pintype "input"))
      (node (ref "IC16") (pin "4") (pinfunction "~{RAS}_4") (pintype "input"))
      (node (ref "IC17") (pin "4") (pinfunction "~{RAS}_4") (pintype "input"))
      (node (ref "IC18") (pin "4") (pinfunction "~{RAS}_4") (pintype "input"))
      (node (ref "IC19") (pin "4") (pinfunction "~{RAS}_4") (pintype "input"))
      (node (ref "IC20") (pin "4") (pinfunction "~{RAS}_4") (pintype "input"))
      (node (ref "IC3") (pin "13") (pinfunction "~{VRAS}_13") (pintype "output"))
      (node (ref "R16") (pin "2") (pinfunction "2_2") (pintype "passive"))
      (node (ref "TP4") (pin "1") (pinfunction "TP_1") (pintype "input"))
    )
    (net (code "72") (name "/~{VWR}") (class "Default")
      (node (ref "IC13") (pin "3") (pinfunction "~{WE}_3") (pintype "input"))
      (node (ref "IC14") (pin "3") (pinfunction "~{WE}_3") (pintype "input"))
      (node (ref "IC15") (pin "3") (pinfunction "~{WE}_3") (pintype "input"))
      (node (ref "IC16") (pin "3") (pinfunction "~{WE}_3") (pintype "input"))
      (node (ref "IC17") (pin "3") (pinfunction "~{WE}_3") (pintype "input"))
      (node (ref "IC18") (pin "3") (pinfunction "~{WE}_3") (pintype "input"))
      (node (ref "IC19") (pin "3") (pinfunction "~{WE}_3") (pintype "input"))
      (node (ref "IC20") (pin "3") (pinfunction "~{WE}_3") (pintype "input"))
      (node (ref "IC3") (pin "14") (pinfunction "~{VWR}_14") (pintype "output"))
      (node (ref "TP6") (pin "1") (pinfunction "TP_1") (pintype "input"))
    )
    (net (code "73") (name "/~{WR}") (class "Default")
      (node (ref "IC1") (pin "22") (pinfunction "~{WR}_22") (pintype "output"))
      (node (ref "IC21") (pin "4") (pinfunction "~{WE}_4") (pintype "input"))
      (node (ref "IC22") (pin "4") (pinfunction "~{WE}_4") (pintype "input"))
      (node (ref "IC23") (pin "4") (pinfunction "~{WE}_4") (pintype "input"))
      (node (ref "IC24") (pin "4") (pinfunction "~{WE}_4") (pintype "input"))
      (node (ref "IC25") (pin "1") (pinfunction "I0_1") (pintype "input"))
      (node (ref "IC3") (pin "16") (pinfunction "~{WR}_16") (pintype "input"))
      (node (ref "U$1") (pin "19B") (pinfunction "EDGE_19B") (pintype "bidirectional"))
    )
    (net (code "74") (name "GND") (class "Default")
      (node (ref "7805") (pin "GND") (pinfunction "GND_GND") (pintype "input"))
      (node (ref "C1") (pin "-") (pinfunction "-_-") (pintype "passive"))
      (node (ref "C10") (pin "2") (pinfunction "2_2") (pintype "passive"))
      (node (ref "C11") (pin "2") (pinfunction "2_2") (pintype "passive"))
      (node (ref "C12") (pin "1") (pinfunction "1_1") (pintype "passive"))
      (node (ref "C13") (pin "1") (pinfunction "1_1") (pintype "passive"))
      (node (ref "C14") (pin "1") (pinfunction "1_1") (pintype "passive"))
      (node (ref "C15") (pin "2") (pinfunction "2_2") (pintype "passive"))
      (node (ref "C16") (pin "2") (pinfunction "2_2") (pintype "passive"))
      (node (ref "C17") (pin "2") (pinfunction "2_2") (pintype "passive"))
      (node (ref "C18") (pin "2") (pinfunction "2_2") (pintype "passive"))
      (node (ref "C19") (pin "2") (pinfunction "2_2") (pintype "passive"))
      (node (ref "C2") (pin "-") (pinfunction "-_-") (pintype "passive"))
      (node (ref "C20") (pin "2") (pinfunction "2_2") (pintype "passive"))
      (node (ref "C21") (pin "2") (pinfunction "2_2") (pintype "passive"))
      (node (ref "C22") (pin "1") (pinfunction "1_1") (pintype "passive"))
      (node (ref "C23") (pin "2") (pinfunction "2_2") (pintype "passive"))
      (node (ref "C24") (pin "1") (pinfunction "1_1") (pintype "passive"))
      (node (ref "C25") (pin "2") (pinfunction "2_2") (pintype "passive"))
      (node (ref "C26") (pin "2") (pinfunction "2_2") (pintype "passive"))
      (node (ref "C27") (pin "2") (pinfunction "2_2") (pintype "passive"))
      (node (ref "C28") (pin "2") (pinfunction "2_2") (pintype "passive"))
      (node (ref "C29") (pin "1") (pinfunction "1_1") (pintype "passive"))
      (node (ref "C3") (pin "1") (pinfunction "1_1") (pintype "passive"))
      (node (ref "C30") (pin "2") (pinfunction "2_2") (pintype "passive"))
      (node (ref "C31") (pin "1") (pinfunction "1_1") (pintype "passive"))
      (node (ref "C32") (pin "1") (pinfunction "1_1") (pintype "passive"))
      (node (ref "C33") (pin "1") (pinfunction "1_1") (pintype "passive"))
      (node (ref "C40") (pin "1") (pinfunction "1_1") (pintype "passive"))
      (node (ref "C43") (pin "1") (pinfunction "1_1") (pintype "passive"))
      (node (ref "C44") (pin "2") (pinfunction "2_2") (pintype "passive"))
      (node (ref "C45") (pin "2") (pinfunction "2_2") (pintype "passive"))
      (node (ref "C46") (pin "2") (pinfunction "2_2") (pintype "passive"))
      (node (ref "C49") (pin "+") (pinfunction "+_+") (pintype "passive"))
      (node (ref "C50") (pin "2") (pinfunction "2_2") (pintype "passive"))
      (node (ref "C52") (pin "-") (pinfunction "-_-") (pintype "passive"))
      (node (ref "C53") (pin "-") (pinfunction "-_-") (pintype "passive"))
      (node (ref "C56") (pin "1") (pinfunction "1_1") (pintype "passive"))
      (node (ref "C57") (pin "2") (pinfunction "2_2") (pintype "passive"))
      (node (ref "C6") (pin "1") (pinfunction "1_1") (pintype "passive"))
      (node (ref "C8") (pin "1") (pinfunction "1_1") (pintype "passive"))
      (node (ref "D14") (pin "A") (pinfunction "A_A") (pintype "passive"))
      (node (ref "D16") (pin "A") (pinfunction "A_A") (pintype "bidirectional"))
      (node (ref "D18") (pin "A") (pinfunction "A_A") (pintype "bidirectional"))
      (node (ref "D20") (pin "C") (pinfunction "K_C") (pintype "bidirectional"))
      (node (ref "D21") (pin "C") (pinfunction "K_C") (pintype "bidirectional"))
      (node (ref "D24") (pin "A") (pinfunction "A_A") (pintype "bidirectional"))
      (node (ref "EAR") (pin "RING") (pinfunction "SHIELD_RING") (pintype "passive"))
      (node (ref "IC1") (pin "29") (pinfunction "GND_29") (pintype "power_in"))
      (node (ref "IC10") (pin "15") (pinfunction "G2_15") (pintype "input"))
      (node (ref "IC10") (pin "8") (pinfunction "GND_8") (pintype "power_in"))
      (node (ref "IC11") (pin "10") (pinfunction "GND_10") (pintype "power_in"))
      (node (ref "IC12") (pin "5") (pinfunction "GND_5") (pintype "power_in"))
      (node (ref "IC13") (pin "16") (pinfunction "VSS_16") (pintype "power_in"))
      (node (ref "IC14") (pin "16") (pinfunction "VSS_16") (pintype "power_in"))
      (node (ref "IC15") (pin "16") (pinfunction "VSS_16") (pintype "power_in"))
      (node (ref "IC16") (pin "16") (pinfunction "VSS_16") (pintype "power_in"))
      (node (ref "IC17") (pin "16") (pinfunction "VSS_16") (pintype "power_in"))
      (node (ref "IC18") (pin "16") (pinfunction "VSS_16") (pintype "power_in"))
      (node (ref "IC19") (pin "16") (pinfunction "VSS_16") (pintype "power_in"))
      (node (ref "IC2") (pin "14") (pinfunction "GND_14") (pintype "power_in"))
      (node (ref "IC20") (pin "16") (pinfunction "VSS_16") (pintype "power_in"))
      (node (ref "IC21") (pin "18") (pinfunction "GND_18") (pintype "power_in"))
      (node (ref "IC22") (pin "18") (pinfunction "GND_18") (pintype "power_in"))
      (node (ref "IC23") (pin "18") (pinfunction "GND_18") (pintype "power_in"))
      (node (ref "IC24") (pin "18") (pinfunction "GND_18") (pintype "power_in"))
      (node (ref "IC25") (pin "7") (pinfunction "GND_7") (pintype "power_in"))
      (node (ref "IC26") (pin "7") (pinfunction "GND_7") (pintype "power_in"))
      (node (ref "IC27") (pin "5") (pinfunction "I1_5") (pintype "input"))
      (node (ref "IC27") (pin "7") (pinfunction "GND_7") (pintype "power_in"))
      (node (ref "IC28") (pin "7") (pinfunction "GND_7") (pintype "power_in"))
      (node (ref "IC3") (pin "20") (pinfunction "GND_20") (pintype "power_in"))
      (node (ref "IC4") (pin "7") (pinfunction "GND_7") (pintype "power_in"))
      (node (ref "IC5") (pin "7") (pinfunction "GND_7") (pintype "power_in"))
      (node (ref "IC6") (pin "15") (pinfunction "G_15") (pintype "input"))
      (node (ref "IC6") (pin "8") (pinfunction "GND_8") (pintype "power_in"))
      (node (ref "IC7") (pin "15") (pinfunction "G_15") (pintype "input"))
      (node (ref "IC7") (pin "8") (pinfunction "GND_8") (pintype "power_in"))
      (node (ref "IC8") (pin "15") (pinfunction "G_15") (pintype "input"))
      (node (ref "IC8") (pin "8") (pinfunction "GND_8") (pintype "power_in"))
      (node (ref "IC9") (pin "15") (pinfunction "G_15") (pintype "input"))
      (node (ref "IC9") (pin "8") (pinfunction "GND_8") (pintype "power_in"))
      (node (ref "MIC") (pin "RING") (pinfunction "SHIELD_RING") (pintype "passive"))
      (node (ref "Q2") (pin "1") (pinfunction "E_1") (pintype "passive"))
      (node (ref "Q4") (pin "1") (pinfunction "E_1") (pintype "passive"))
      (node (ref "Q6") (pin "C") (pinfunction "C_C") (pintype "passive"))
      (node (ref "Q7") (pin "1") (pinfunction "E_1") (pintype "passive"))
      (node (ref "R33") (pin "2") (pinfunction "2_2") (pintype "passive"))
      (node (ref "R41") (pin "1") (pinfunction "1_1") (pintype "passive"))
      (node (ref "R47") (pin "1") (pinfunction "1_1") (pintype "passive"))
      (node (ref "R50") (pin "1") (pinfunction "1_1") (pintype "passive"))
      (node (ref "R53") (pin "2") (pinfunction "2_2") (pintype "passive"))
      (node (ref "R55") (pin "2") (pinfunction "2_2") (pintype "passive"))
      (node (ref "R60") (pin "2") (pinfunction "2_2") (pintype "passive"))
      (node (ref "R65") (pin "2") (pinfunction "2_2") (pintype "passive"))
      (node (ref "R69") (pin "1") (pinfunction "1_1") (pintype "passive"))
      (node (ref "R70") (pin "1") (pinfunction "1_1") (pintype "passive"))
      (node (ref "R73_") (pin "2") (pinfunction "2_2") (pintype "passive"))
      (node (ref "U$1") (pin "14A") (pinfunction "EDGE_14A") (pintype "bidirectional"))
      (node (ref "U$1") (pin "6A") (pinfunction "EDGE_6A") (pintype "bidirectional"))
      (node (ref "U$1") (pin "7A") (pinfunction "EDGE_7A") (pintype "bidirectional"))
      (node (ref "X2") (pin "RING") (pinfunction "SHIELD_RING") (pintype "passive"))
    )
    (net (code "75") (name "Net-(C5-Pad1)") (class "Default")
      (node (ref "C5") (pin "1") (pinfunction "1_1") (pintype "passive"))
      (node (ref "R42") (pin "1") (pinfunction "1_1") (pintype "passive"))
    )
    (net (code "76") (name "Net-(C5-Pad2)") (class "Default")
      (node (ref "C5") (pin "2") (pinfunction "2_2") (pintype "passive"))
      (node (ref "EAR") (pin "NC") (pinfunction "NC_NC") (pintype "passive"))
      (node (ref "EAR") (pin "TIP") (pinfunction "TIP_TIP") (pintype "passive"))
      (node (ref "R70") (pin "2") (pinfunction "2_2") (pintype "passive"))
    )
    (net (code "77") (name "Net-(C7-Pad1)") (class "Default")
      (node (ref "C7") (pin "1") (pinfunction "1_1") (pintype "passive"))
      (node (ref "XTAL") (pin "2") (pinfunction "2_2") (pintype "passive"))
    )
    (net (code "78") (name "Net-(C8-Pad2)") (class "Default")
      (node (ref "C8") (pin "2") (pinfunction "2_2") (pintype "passive"))
      (node (ref "Q3") (pin "B") (pinfunction "B_B") (pintype "passive"))
      (node (ref "R44") (pin "2") (pinfunction "2_2") (pintype "passive"))
      (node (ref "XTAL") (pin "1") (pinfunction "1_1") (pintype "passive"))
    )
    (net (code "79") (name "Net-(C34-Pad2)") (class "Default")
      (node (ref "C34") (pin "2") (pinfunction "2_2") (pintype "passive"))
      (node (ref "R52") (pin "2") (pinfunction "2_2") (pintype "passive"))
    )
    (net (code "80") (name "Net-(C36-Pad2)") (class "Default")
      (node (ref "C36") (pin "2") (pinfunction "2_2") (pintype "passive"))
      (node (ref "C54") (pin "2") (pinfunction "2_2") (pintype "passive"))
      (node (ref "C55") (pin "1") (pinfunction "1_1") (pintype "passive"))
      (node (ref "D25_") (pin "A") (pinfunction "A_A") (pintype "bidirectional"))
      (node (ref "R53") (pin "1") (pinfunction "1_1") (pintype "passive"))
      (node (ref "R54") (pin "2") (pinfunction "2_2") (pintype "passive"))
    )
    (net (code "81") (name "Net-(C37-Pad1)") (class "Default")
      (node (ref "C37") (pin "1") (pinfunction "1_1") (pintype "passive"))
      (node (ref "C38") (pin "2") (pinfunction "2_2") (pintype "passive"))
      (node (ref "R55") (pin "1") (pinfunction "1_1") (pintype "passive"))
    )
    (net (code "82") (name "Net-(C38-Pad1)") (class "Default")
      (node (ref "C38") (pin "1") (pinfunction "1_1") (pintype "passive"))
      (node (ref "C39") (pin "2") (pinfunction "2_2") (pintype "passive"))
      (node (ref "R56") (pin "1") (pinfunction "1_1") (pintype "passive"))
    )
    (net (code "83") (name "Net-(C39-Pad1)") (class "Default")
      (node (ref "C39") (pin "1") (pinfunction "1_1") (pintype "passive"))
      (node (ref "L2") (pin "2") (pinfunction "2_2") (pintype "passive"))
    )
    (net (code "84") (name "Net-(C49-Pad-)") (class "Default")
      (node (ref "C49") (pin "-") (pinfunction "-_-") (pintype "passive"))
      (node (ref "D19") (pin "A") (pinfunction "A_A") (pintype "bidirectional"))
      (node (ref "R67") (pin "2") (pinfunction "2_2") (pintype "passive"))
    )
    (net (code "85") (name "Net-(C56-Pad2)") (class "Default")
      (node (ref "C56") (pin "2") (pinfunction "2_2") (pintype "passive"))
      (node (ref "L2") (pin "1") (pinfunction "1_1") (pintype "passive"))
      (node (ref "R71") (pin "1") (pinfunction "1_1") (pintype "passive"))
      (node (ref "R72") (pin "2") (pinfunction "2_2") (pintype "passive"))
    )
    (net (code "86") (name "Net-(D2-PadA)") (class "Default")
      (node (ref "D2") (pin "A") (pinfunction "A_A") (pintype "bidirectional"))
      (node (ref "KB2") (pin "3") (pinfunction "3_3") (pintype "passive"))
    )
    (net (code "87") (name "Net-(D3-PadA)") (class "Default")
      (node (ref "D3") (pin "A") (pinfunction "A_A") (pintype "bidirectional"))
      (node (ref "KB2") (pin "6") (pinfunction "6_6") (pintype "passive"))
    )
    (net (code "88") (name "Net-(D4-PadA)") (class "Default")
      (node (ref "D4") (pin "A") (pinfunction "A_A") (pintype "bidirectional"))
      (node (ref "KB2") (pin "7") (pinfunction "7_7") (pintype "passive"))
    )
    (net (code "89") (name "Net-(D7-PadA)") (class "Default")
      (node (ref "D7") (pin "A") (pinfunction "A_A") (pintype "bidirectional"))
      (node (ref "KB2") (pin "4") (pinfunction "4_4") (pintype "passive"))
    )
    (net (code "90") (name "Net-(D8-PadA)") (class "Default")
      (node (ref "D8") (pin "A") (pinfunction "A_A") (pintype "bidirectional"))
      (node (ref "KB2") (pin "2") (pinfunction "2_2") (pintype "passive"))
    )
    (net (code "91") (name "Net-(D9-PadA)") (class "Default")
      (node (ref "D9") (pin "A") (pinfunction "A_A") (pintype "bidirectional"))
      (node (ref "KB2") (pin "1") (pinfunction "1_1") (pintype "passive"))
    )
    (net (code "92") (name "Net-(D11-K)") (class "Default")
      (node (ref "D11") (pin "C") (pinfunction "K_C") (pintype "bidirectional"))
      (node (ref "D12") (pin "C") (pinfunction "K_C") (pintype "bidirectional"))
      (node (ref "IC27") (pin "11") (pinfunction "O_11") (pintype "output"))
      (node (ref "R26") (pin "1") (pinfunction "1_1") (pintype "passive"))
      (node (ref "R33") (pin "1") (pinfunction "1_1") (pintype "passive"))
    )
    (net (code "93") (name "Net-(D16-K)") (class "Default")
      (node (ref "C36") (pin "1") (pinfunction "1_1") (pintype "passive"))
      (node (ref "D15") (pin "A") (pinfunction "A_A") (pintype "bidirectional"))
      (node (ref "D16") (pin "C") (pinfunction "K_C") (pintype "bidirectional"))
      (node (ref "IC3") (pin "24") (pinfunction "BEEP_24") (pintype "output"))
      (node (ref "TP7") (pin "1") (pinfunction "TP_1") (pintype "input"))
    )
    (net (code "94") (name "Net-(D19-K)") (class "Default")
      (node (ref "C48") (pin "2") (pinfunction "2_2") (pintype "passive"))
      (node (ref "D19") (pin "C") (pinfunction "K_C") (pintype "bidirectional"))
      (node (ref "D20") (pin "A") (pinfunction "A_A") (pintype "bidirectional"))
    )
    (net (code "95") (name "Net-(D22-K)") (class "Default")
      (node (ref "C51") (pin "2") (pinfunction "2_2") (pintype "passive"))
      (node (ref "D22") (pin "C") (pinfunction "K_C") (pintype "bidirectional"))
      (node (ref "D23") (pin "A") (pinfunction "A_A") (pintype "bidirectional"))
    )
    (net (code "96") (name "Net-(D23-K)") (class "Default")
      (node (ref "C52") (pin "+") (pinfunction "+_+") (pintype "passive"))
      (node (ref "D23") (pin "C") (pinfunction "K_C") (pintype "bidirectional"))
      (node (ref "R68") (pin "2") (pinfunction "2_2") (pintype "passive"))
    )
    (net (code "97") (name "Net-(D27-K)") (class "Default")
      (node (ref "D25") (pin "C") (pinfunction "C_C") (pintype "passive"))
      (node (ref "D26") (pin "C") (pinfunction "C_C") (pintype "passive"))
      (node (ref "D27") (pin "C") (pinfunction "K_C") (pintype "bidirectional"))
      (node (ref "IC3") (pin "18") (pinfunction "BRIGHT_18") (pintype "output"))
    )
    (net (code "98") (name "Net-(IC1-CLK)") (class "Default")
      (node (ref "IC1") (pin "6") (pinfunction "CLK_6") (pintype "input"))
      (node (ref "Q2") (pin "3") (pinfunction "C_3") (pintype "passive"))
      (node (ref "R48") (pin "1") (pinfunction "1_1") (pintype "passive"))
      (node (ref "TP1") (pin "1") (pinfunction "TP_1") (pintype "input"))
    )
    (net (code "99") (name "Net-(IC1-~{BUSAK})") (class "Default")
      (node (ref "IC1") (pin "23") (pinfunction "~{BUSAK}_23") (pintype "output"))
      (node (ref "U$1") (pin "26A") (pinfunction "EDGE_26A") (pintype "bidirectional"))
    )
    (net (code "100") (name "Net-(IC1-~{BUSRQ})") (class "Default")
      (node (ref "IC1") (pin "25") (pinfunction "~{BUSRQ}_25") (pintype "input"))
      (node (ref "R30") (pin "2") (pinfunction "2_2") (pintype "passive"))
      (node (ref "U$1") (pin "19A") (pinfunction "EDGE_19A") (pintype "bidirectional"))
    )
    (net (code "101") (name "Net-(IC1-~{HALT})") (class "Default")
      (node (ref "IC1") (pin "18") (pinfunction "~{HALT}_18") (pintype "output"))
      (node (ref "U$1") (pin "15B") (pinfunction "EDGE_15B") (pintype "bidirectional"))
    )
    (net (code "102") (name "Net-(IC1-~{M1})") (class "Default")
      (node (ref "IC1") (pin "27") (pinfunction "~{M1}_27") (pintype "output"))
      (node (ref "U$1") (pin "24B") (pinfunction "EDGE_24B") (pintype "bidirectional"))
    )
    (net (code "103") (name "Net-(IC1-~{NMI})") (class "Default")
      (node (ref "IC1") (pin "17") (pinfunction "~{NMI}_17") (pintype "input"))
      (node (ref "R31") (pin "2") (pinfunction "2_2") (pintype "passive"))
      (node (ref "U$1") (pin "14B") (pinfunction "EDGE_14B") (pintype "bidirectional"))
    )
    (net (code "104") (name "Net-(IC1-~{WAIT})") (class "Default")
      (node (ref "IC1") (pin "24") (pinfunction "~{WAIT}_24") (pintype "input"))
      (node (ref "R32") (pin "2") (pinfunction "2_2") (pintype "passive"))
      (node (ref "U$1") (pin "21B") (pinfunction "EDGE_21B") (pintype "bidirectional"))
    )
    (net (code "105") (name "Net-(IC3-MIC)") (class "Default")
      (node (ref "IC3") (pin "23") (pinfunction "MIC_23") (pintype "output"))
      (node (ref "R46") (pin "2") (pinfunction "2_2") (pintype "passive"))
    )
    (net (code "106") (name "Net-(IC4B-D)") (class "Default")
      (node (ref "IC4") (pin "12") (pinfunction "D_12") (pintype "input"))
      (node (ref "IC4") (pin "8") (pinfunction "~{Q}_8") (pintype "output"))
    )
    (net (code "107") (name "Net-(IC5A-CLK)") (class "Default")
      (node (ref "IC5") (pin "3") (pinfunction "CLK_3") (pintype "input"))
      (node (ref "IC5") (pin "9") (pinfunction "Q_9") (pintype "output"))
    )
    (net (code "108") (name "Net-(IC5A-D)") (class "Default")
      (node (ref "IC5") (pin "2") (pinfunction "D_2") (pintype "input"))
      (node (ref "IC5") (pin "6") (pinfunction "~{Q}_6") (pintype "output"))
    )
    (net (code "109") (name "Net-(IC8A-1Y)") (class "Default")
      (node (ref "IC8") (pin "4") (pinfunction "1Y_4") (pintype "output"))
      (node (ref "R15") (pin "2") (pinfunction "2_2") (pintype "passive"))
    )
    (net (code "110") (name "Net-(IC8A-2Y)") (class "Default")
      (node (ref "IC8") (pin "7") (pinfunction "2Y_7") (pintype "output"))
      (node (ref "R14") (pin "2") (pinfunction "2_2") (pintype "passive"))
    )
    (net (code "111") (name "Net-(IC8A-3Y)") (class "Default")
      (node (ref "IC8") (pin "9") (pinfunction "3Y_9") (pintype "output"))
      (node (ref "R12") (pin "2") (pinfunction "2_2") (pintype "passive"))
    )
    (net (code "112") (name "Net-(IC8A-4Y)") (class "Default")
      (node (ref "IC8") (pin "12") (pinfunction "4Y_12") (pintype "output"))
      (node (ref "R13") (pin "2") (pinfunction "2_2") (pintype "passive"))
    )
    (net (code "113") (name "Net-(IC8A-~{A}{slash}B)") (class "Default")
      (node (ref "IC8") (pin "1") (pinfunction "~{A}/B_1") (pintype "input"))
      (node (ref "IC9") (pin "1") (pinfunction "~{A}/B_1") (pintype "input"))
      (node (ref "R16") (pin "1") (pinfunction "1_1") (pintype "passive"))
    )
    (net (code "114") (name "Net-(IC9A-2Y)") (class "Default")
      (node (ref "IC9") (pin "7") (pinfunction "2Y_7") (pintype "output"))
      (node (ref "R11") (pin "2") (pinfunction "2_2") (pintype "passive"))
    )
    (net (code "115") (name "Net-(IC9A-3Y)") (class "Default")
      (node (ref "IC9") (pin "9") (pinfunction "3Y_9") (pintype "output"))
      (node (ref "R9") (pin "2") (pinfunction "2_2") (pintype "passive"))
    )
    (net (code "116") (name "Net-(IC9A-4Y)") (class "Default")
      (node (ref "IC9") (pin "12") (pinfunction "4Y_12") (pintype "output"))
      (node (ref "R10") (pin "2") (pinfunction "2_2") (pintype "passive"))
    )
    (net (code "117") (name "Net-(IC10A-A1)") (class "Default")
      (node (ref "IC10") (pin "2") (pinfunction "A1_2") (pintype "input"))
      (node (ref "KB1") (pin "5") (pinfunction "5_5") (pintype "passive"))
      (node (ref "P") (pin "6") (pinfunction "M_6") (pintype "passive"))
      (node (ref "R39") (pin "2") (pinfunction "2_2") (pintype "passive"))
    )
    (net (code "118") (name "Net-(IC10A-A2)") (class "Default")
      (node (ref "IC10") (pin "4") (pinfunction "A2_4") (pintype "input"))
      (node (ref "KB1") (pin "4") (pinfunction "4_4") (pintype "passive"))
      (node (ref "P") (pin "1") (pinfunction "M_1") (pintype "passive"))
      (node (ref "R38") (pin "2") (pinfunction "2_2") (pintype "passive"))
    )
    (net (code "119") (name "Net-(IC10A-A3)") (class "Default")
      (node (ref "IC10") (pin "6") (pinfunction "A3_6") (pintype "input"))
      (node (ref "KB1") (pin "3") (pinfunction "3_3") (pintype "passive"))
      (node (ref "P") (pin "2") (pinfunction "M_2") (pintype "passive"))
      (node (ref "R35") (pin "2") (pinfunction "2_2") (pintype "passive"))
    )
    (net (code "120") (name "Net-(IC10A-A4)") (class "Default")
      (node (ref "IC10") (pin "10") (pinfunction "A4_10") (pintype "input"))
      (node (ref "KB1") (pin "2") (pinfunction "2_2") (pintype "passive"))
      (node (ref "P") (pin "4") (pinfunction "M_4") (pintype "passive"))
      (node (ref "R36") (pin "2") (pinfunction "2_2") (pintype "passive"))
    )
    (net (code "121") (name "Net-(IC10A-A5)") (class "Default")
      (node (ref "IC10") (pin "12") (pinfunction "A5_12") (pintype "input"))
      (node (ref "KB1") (pin "1") (pinfunction "1_1") (pintype "passive"))
      (node (ref "P") (pin "3") (pinfunction "M_3") (pintype "passive"))
      (node (ref "R37") (pin "2") (pinfunction "2_2") (pintype "passive"))
    )
    (net (code "122") (name "Net-(IC10A-A6)") (class "Default")
      (node (ref "IC10") (pin "14") (pinfunction "A6_14") (pintype "input"))
      (node (ref "Q7") (pin "3") (pinfunction "C_3") (pintype "passive"))
      (node (ref "R74_") (pin "1") (pinfunction "1_1") (pintype "passive"))
    )
    (net (code "123") (name "Net-(IC11-B-Y)") (class "Default")
      (node (ref "C45") (pin "1") (pinfunction "1_1") (pintype "passive"))
      (node (ref "IC11") (pin "4") (pinfunction "B-Y_4") (pintype "output"))
      (node (ref "IC12") (pin "4") (pinfunction "B-Y_4") (pintype "input"))
    )
    (net (code "124") (name "Net-(IC11-B1)") (class "Default")
      (node (ref "IC11") (pin "17") (pinfunction "B3_17") (pintype "input"))
      (node (ref "IC11") (pin "19") (pinfunction "B1_19") (pintype "input"))
      (node (ref "IC3") (pin "22") (pinfunction "BLUE_22") (pintype "output"))
      (node (ref "R75") (pin "2") (pinfunction "2_2") (pintype "passive"))
    )
    (net (code "125") (name "Net-(IC11-B2)") (class "Default")
      (node (ref "D27") (pin "A") (pinfunction "A_A") (pintype "bidirectional"))
      (node (ref "IC11") (pin "18") (pinfunction "B2_18") (pintype "input"))
      (node (ref "R75") (pin "1") (pinfunction "1_1") (pintype "passive"))
    )
    (net (code "126") (name "Net-(IC11-BLANK)") (class "Default")
      (node (ref "IC11") (pin "8") (pinfunction "SYNC_8") (pintype "input"))
      (node (ref "IC11") (pin "9") (pinfunction "BLANK_9") (pintype "input"))
      (node (ref "IC3") (pin "33") (pinfunction "SYNC_33") (pintype "output"))
      (node (ref "TP8") (pin "1") (pinfunction "TP_1") (pintype "input"))
    )
    (net (code "127") (name "Net-(IC11-CREF)") (class "Default")
      (node (ref "C46") (pin "1") (pinfunction "1_1") (pintype "passive"))
      (node (ref "IC11") (pin "7") (pinfunction "CREF_7") (pintype "input"))
      (node (ref "IC12") (pin "12") (pinfunction "Y_12") (pintype "input"))
    )
    (net (code "128") (name "Net-(IC11-G1)") (class "Default")
      (node (ref "IC11") (pin "14") (pinfunction "G3_14") (pintype "input"))
      (node (ref "IC11") (pin "16") (pinfunction "G1_16") (pintype "input"))
      (node (ref "IC3") (pin "19") (pinfunction "GREEN_19") (pintype "output"))
      (node (ref "R73") (pin "2") (pinfunction "2_2") (pintype "passive"))
    )
    (net (code "129") (name "Net-(IC11-G2)") (class "Default")
      (node (ref "D25") (pin "A") (pinfunction "A_A") (pintype "passive"))
      (node (ref "IC11") (pin "15") (pinfunction "G2_15") (pintype "input"))
      (node (ref "R73") (pin "1") (pinfunction "1_1") (pintype "passive"))
    )
    (net (code "130") (name "Net-(IC11-GATE)") (class "Default")
      (node (ref "IC11") (pin "1") (pinfunction "GATE_1") (pintype "input"))
      (node (ref "IC28") (pin "6") (pinfunction "O_6") (pintype "output"))
    )
    (net (code "131") (name "Net-(IC11-H{slash}2)") (class "Default")
      (node (ref "IC11") (pin "2") (pinfunction "H/2_2") (pintype "input"))
      (node (ref "IC4") (pin "9") (pinfunction "Q_9") (pintype "output"))
    )
    (net (code "132") (name "Net-(IC11-R-Y)") (class "Default")
      (node (ref "C44") (pin "1") (pinfunction "1_1") (pintype "passive"))
      (node (ref "IC11") (pin "3") (pinfunction "R-Y_3") (pintype "output"))
      (node (ref "IC12") (pin "2") (pinfunction "R-Y_2") (pintype "input"))
    )
    (net (code "133") (name "Net-(IC11-R1)") (class "Default")
      (node (ref "IC11") (pin "11") (pinfunction "R3_11") (pintype "input"))
      (node (ref "IC11") (pin "13") (pinfunction "R1_13") (pintype "input"))
      (node (ref "IC3") (pin "21") (pinfunction "RED_21") (pintype "output"))
      (node (ref "R74") (pin "2") (pinfunction "2_2") (pintype "passive"))
    )
    (net (code "134") (name "Net-(IC11-R2)") (class "Default")
      (node (ref "D26") (pin "A") (pinfunction "A_A") (pintype "passive"))
      (node (ref "IC11") (pin "12") (pinfunction "R2_12") (pintype "input"))
      (node (ref "R74") (pin "1") (pinfunction "1_1") (pintype "passive"))
    )
    (net (code "135") (name "Net-(IC11-Y)") (class "Default")
      (node (ref "IC11") (pin "6") (pinfunction "Y_6") (pintype "output"))
      (node (ref "R63") (pin "2") (pinfunction "2_2") (pintype "passive"))
    )
    (net (code "136") (name "Net-(IC12-CHB_O)") (class "Default")
      (node (ref "C42") (pin "1") (pinfunction "1_1") (pintype "passive"))
      (node (ref "IC12") (pin "10") (pinfunction "CHB_O_10") (pintype "input"))
      (node (ref "R59") (pin "2") (pinfunction "2_2") (pintype "passive"))
    )
    (net (code "137") (name "Net-(IC12-CR_LAG)") (class "Default")
      (node (ref "C40") (pin "2") (pinfunction "2_2") (pintype "passive"))
      (node (ref "IC12") (pin "18") (pinfunction "CR_LAG_18") (pintype "output"))
      (node (ref "R56") (pin "2") (pinfunction "2_2") (pintype "passive"))
    )
    (net (code "138") (name "Net-(IC12-CR_LEAD)") (class "Default")
      (node (ref "C37") (pin "2") (pinfunction "2_2") (pintype "passive"))
      (node (ref "IC12") (pin "1") (pinfunction "CR_LEAD_1") (pintype "input"))
    )
    (net (code "139") (name "Net-(IC12-CR_OSC)") (class "Default")
      (node (ref "IC12") (pin "17") (pinfunction "CR_OSC_17") (pintype "input"))
      (node (ref "R72") (pin "1") (pinfunction "1_1") (pintype "passive"))
      (node (ref "R73_") (pin "1") (pinfunction "1_1") (pintype "passive"))
    )
    (net (code "140") (name "Net-(IC12-CR_SUBC)") (class "Default")
      (node (ref "C34") (pin "1") (pinfunction "1_1") (pintype "passive"))
      (node (ref "IC12") (pin "13") (pinfunction "CR_SUBC_13") (pintype "input"))
      (node (ref "R63") (pin "1") (pinfunction "1_1") (pintype "passive"))
    )
    (net (code "141") (name "Net-(IC12-SNDTK)") (class "Default")
      (node (ref "D25_") (pin "K") (pinfunction "K_K") (pintype "bidirectional"))
      (node (ref "IC12") (pin "15") (pinfunction "SNDTK_15") (pintype "input"))
      (node (ref "L1") (pin "4") (pinfunction "E_4") (pintype "passive"))
      (node (ref "R52") (pin "1") (pinfunction "1_1") (pintype "passive"))
    )
    (net (code "142") (name "Net-(IC12-TNKA1)") (class "Default")
      (node (ref "IC12") (pin "8") (pinfunction "TNKA1_8") (pintype "output"))
      (node (ref "IC12") (pin "9") (pinfunction "TNKA2_9") (pintype "input"))
    )
    (net (code "143") (name "Net-(IC12-TNKB1)") (class "Default")
      (node (ref "C41") (pin "2") (pinfunction "2_2") (pintype "passive"))
      (node (ref "IC12") (pin "6") (pinfunction "TNKB1_6") (pintype "output"))
      (node (ref "L3") (pin "1") (pinfunction "1_1") (pintype "passive"))
      (node (ref "R57") (pin "2") (pinfunction "2_2") (pintype "passive"))
    )
    (net (code "144") (name "Net-(IC12-TNKB2)") (class "Default")
      (node (ref "C41") (pin "1") (pinfunction "1_1") (pintype "passive"))
      (node (ref "IC12") (pin "7") (pinfunction "TNKB2_7") (pintype "input"))
      (node (ref "L3") (pin "2") (pinfunction "2_2") (pintype "passive"))
      (node (ref "R58") (pin "2") (pinfunction "2_2") (pintype "passive"))
    )
    (net (code "145") (name "Net-(IC25A-O)") (class "Default")
      (node (ref "IC25") (pin "12") (pinfunction "I0_12") (pintype "input"))
      (node (ref "IC25") (pin "3") (pinfunction "O_3") (pintype "output"))
    )
    (net (code "146") (name "Net-(IC25B-I1)") (class "Default")
      (node (ref "IC25") (pin "10") (pinfunction "I1_10") (pintype "input"))
      (node (ref "IC25") (pin "5") (pinfunction "I1_5") (pintype "input"))
      (node (ref "IC28") (pin "4") (pinfunction "O_4") (pintype "output"))
    )
    (net (code "147") (name "Net-(IC25C-I0)") (class "Default")
      (node (ref "IC25") (pin "9") (pinfunction "I0_9") (pintype "input"))
      (node (ref "IC28") (pin "2") (pinfunction "O_2") (pintype "output"))
    )
    (net (code "148") (name "Net-(IC25D-O)") (class "Default")
      (node (ref "IC25") (pin "11") (pinfunction "O_11") (pintype "output"))
      (node (ref "IC27") (pin "1") (pinfunction "I0_1") (pintype "input"))
    )
    (net (code "149") (name "Net-(IC26A-O)") (class "Default")
      (node (ref "IC26") (pin "3") (pinfunction "O_3") (pintype "output"))
      (node (ref "IC26") (pin "4") (pinfunction "I0_4") (pintype "input"))
    )
    (net (code "150") (name "Net-(IC26B-I1)") (class "Default")
      (node (ref "IC26") (pin "5") (pinfunction "I1_5") (pintype "input"))
      (node (ref "IC5") (pin "5") (pinfunction "Q_5") (pintype "output"))
    )
    (net (code "151") (name "Net-(IC26B-O)") (class "Default")
      (node (ref "IC26") (pin "6") (pinfunction "O_6") (pintype "output"))
      (node (ref "IC26") (pin "9") (pinfunction "I0_9") (pintype "input"))
    )
    (net (code "152") (name "Net-(IC26C-I1)") (class "Default")
      (node (ref "IC26") (pin "10") (pinfunction "I1_10") (pintype "input"))
      (node (ref "IC26") (pin "11") (pinfunction "O_11") (pintype "output"))
    )
    (net (code "153") (name "Net-(IC27A-I1)") (class "Default")
      (node (ref "C10") (pin "1") (pinfunction "1_1") (pintype "passive"))
      (node (ref "IC27") (pin "2") (pinfunction "I1_2") (pintype "input"))
      (node (ref "R28") (pin "2") (pinfunction "2_2") (pintype "passive"))
    )
    (net (code "154") (name "Net-(IC27C-I1)") (class "Default")
      (node (ref "C11") (pin "1") (pinfunction "1_1") (pintype "passive"))
      (node (ref "IC27") (pin "10") (pinfunction "I1_10") (pintype "input"))
      (node (ref "R45") (pin "2") (pinfunction "2_2") (pintype "passive"))
    )
    (net (code "155") (name "Net-(IC27C-O)") (class "Default")
      (node (ref "IC27") (pin "8") (pinfunction "O_8") (pintype "output"))
      (node (ref "IC28") (pin "3") (pinfunction "I_3") (pintype "input"))
    )
    (net (code "156") (name "Net-(IC28C-I)") (class "Default")
      (node (ref "IC28") (pin "5") (pinfunction "I_5") (pintype "input"))
      (node (ref "IC3") (pin "35") (pinfunction "GATE_35") (pintype "output"))
      (node (ref "IC4") (pin "11") (pinfunction "CLK_11") (pintype "input"))
    )
    (net (code "157") (name "Net-(IC28D-I)") (class "Default")
      (node (ref "C6") (pin "2") (pinfunction "2_2") (pintype "passive"))
      (node (ref "C7") (pin "2") (pinfunction "2_2") (pintype "passive"))
      (node (ref "IC28") (pin "9") (pinfunction "I_9") (pintype "input"))
      (node (ref "Q3") (pin "C") (pinfunction "C_C") (pintype "passive"))
      (node (ref "R43") (pin "1") (pinfunction "1_1") (pintype "passive"))
      (node (ref "R44") (pin "1") (pinfunction "1_1") (pintype "passive"))
    )
    (net (code "158") (name "Net-(IC28D-O)") (class "Default")
      (node (ref "IC28") (pin "11") (pinfunction "I_11") (pintype "input"))
      (node (ref "IC28") (pin "8") (pinfunction "O_8") (pintype "output"))
      (node (ref "JP") (pin "3") (pinfunction "3_3") (pintype "passive"))
    )
    (net (code "159") (name "Net-(IC28E-O)") (class "Default")
      (node (ref "IC28") (pin "10") (pinfunction "O_10") (pintype "output"))
      (node (ref "IC3") (pin "11") (pinfunction "CLK_11") (pintype "input"))
      (node (ref "JP") (pin "1") (pinfunction "1_1") (pintype "passive"))
      (node (ref "JP") (pin "2") (pinfunction "2_2") (pintype "passive"))
      (node (ref "TP2") (pin "1") (pinfunction "TP_1") (pintype "input"))
    )
    (net (code "160") (name "Net-(MIC-PadNC)") (class "Default")
      (node (ref "MIC") (pin "NC") (pinfunction "NC_NC") (pintype "passive"))
      (node (ref "MIC") (pin "TIP") (pinfunction "TIP_TIP") (pintype "passive"))
      (node (ref "R46") (pin "1") (pinfunction "1_1") (pintype "passive"))
      (node (ref "R69") (pin "2") (pinfunction "2_2") (pintype "passive"))
    )
    (net (code "161") (name "Net-(PE-M)") (class "Default")
      (node (ref "D6") (pin "A") (pinfunction "A_A") (pintype "bidirectional"))
      (node (ref "KB2") (pin "5") (pinfunction "5_5") (pintype "passive"))
      (node (ref "P") (pin "5") (pinfunction "M_5") (pintype "passive"))
      (node (ref "P") (pin "8") (pinfunction "M_8") (pintype "passive"))
      (node (ref "P") (pin "9") (pinfunction "M_9") (pintype "passive"))
    )
    (net (code "162") (name "Net-(PG-M)") (class "Default")
      (node (ref "D5") (pin "A") (pinfunction "A_A") (pintype "bidirectional"))
      (node (ref "KB2") (pin "8") (pinfunction "8_8") (pintype "passive"))
      (node (ref "P") (pin "7") (pinfunction "M_7") (pintype "passive"))
    )
    (net (code "163") (name "Net-(Q2-B)") (class "Default")
      (node (ref "C9") (pin "1") (pinfunction "1_1") (pintype "passive"))
      (node (ref "Q2") (pin "2") (pinfunction "B_2") (pintype "passive"))
      (node (ref "R49") (pin "1") (pinfunction "1_1") (pintype "passive"))
      (node (ref "R50") (pin "2") (pinfunction "2_2") (pintype "passive"))
    )
    (net (code "164") (name "Net-(Q3-PadE)") (class "Default")
      (node (ref "Q3") (pin "E") (pinfunction "E_E") (pintype "passive"))
      (node (ref "R47") (pin "2") (pinfunction "2_2") (pintype "passive"))
    )
    (net (code "165") (name "Net-(Q4-B)") (class "Default")
      (node (ref "C47") (pin "2") (pinfunction "2_2") (pintype "passive"))
      (node (ref "Q4") (pin "2") (pinfunction "B_2") (pintype "passive"))
      (node (ref "R64") (pin "1") (pinfunction "1_1") (pintype "passive"))
      (node (ref "R65") (pin "1") (pinfunction "1_1") (pintype "passive"))
    )
    (net (code "166") (name "Net-(Q4-C)") (class "Default")
      (node (ref "Q4") (pin "3") (pinfunction "C_3") (pintype "passive"))
      (node (ref "Q5") (pin "B") (pinfunction "B_B") (pintype "passive"))
      (node (ref "Q6") (pin "B") (pinfunction "B_B") (pintype "passive"))
      (node (ref "R66") (pin "2") (pinfunction "2_2") (pintype "passive"))
    )
    (net (code "167") (name "Net-(U$1Y-EDGE)") (class "Default")
      (node (ref "C55") (pin "2") (pinfunction "2_2") (pintype "passive"))
      (node (ref "U$1") (pin "4B") (pinfunction "EDGE_4B") (pintype "bidirectional"))
    )
    (net (code "168") (name "Net-(VIDEO(RF)-TP)") (class "Default")
      (node (ref "C42") (pin "2") (pinfunction "2_2") (pintype "passive"))
      (node (ref "R60") (pin "1") (pinfunction "1_1") (pintype "passive"))
      (node (ref "VIDEO(RF)") (pin "1") (pinfunction "TP_1") (pintype "input"))
    )
    (net (code "169") (name "V+") (class "Default")
      (node (ref "7805") (pin "IN") (pinfunction "IN_IN") (pintype "input"))
      (node (ref "C2") (pin "+") (pinfunction "+_+") (pintype "passive"))
      (node (ref "C23") (pin "1") (pinfunction "1_1") (pintype "passive"))
      (node (ref "C25") (pin "1") (pinfunction "1_1") (pintype "passive"))
      (node (ref "C28") (pin "1") (pinfunction "1_1") (pintype "passive"))
      (node (ref "C3") (pin "2") (pinfunction "2_2") (pintype "passive"))
      (node (ref "C30") (pin "1") (pinfunction "1_1") (pintype "passive"))
      (node (ref "D22") (pin "A") (pinfunction "A_A") (pintype "bidirectional"))
      (node (ref "IC13") (pin "8") (pinfunction "VDD_8") (pintype "power_in"))
      (node (ref "IC14") (pin "8") (pinfunction "VDD_8") (pintype "power_in"))
      (node (ref "IC15") (pin "8") (pinfunction "VDD_8") (pintype "power_in"))
      (node (ref "IC16") (pin "8") (pinfunction "VDD_8") (pintype "power_in"))
      (node (ref "IC17") (pin "8") (pinfunction "VDD_8") (pintype "power_in"))
      (node (ref "IC18") (pin "8") (pinfunction "VDD_8") (pintype "power_in"))
      (node (ref "IC19") (pin "8") (pinfunction "VDD_8") (pintype "power_in"))
      (node (ref "IC20") (pin "8") (pinfunction "VDD_8") (pintype "power_in"))
      (node (ref "Q5") (pin "C") (pinfunction "C_C") (pintype "passive"))
      (node (ref "R66") (pin "1") (pinfunction "1_1") (pintype "passive"))
      (node (ref "U$1") (pin "4A") (pinfunction "EDGE_4A") (pintype "bidirectional"))
      (node (ref "X2") (pin "TIP") (pinfunction "TIP_TIP") (pintype "passive"))
    )
    (net (code "170") (name "unconnected-(IC3-~{50}{slash}60HZ-Pad1)") (class "Default")
      (node (ref "IC3") (pin "1") (pinfunction "~{50}/60HZ_1") (pintype "input"))
    )
    (net (code "171") (name "unconnected-(IC4A-CLK-Pad3)") (class "Default")
      (node (ref "IC4") (pin "3") (pinfunction "CLK_3") (pintype "input"))
    )
    (net (code "172") (name "unconnected-(IC4A-CLR-Pad1)") (class "Default")
      (node (ref "IC4") (pin "1") (pinfunction "CLR_1") (pintype "input"))
    )
    (net (code "173") (name "unconnected-(IC4A-D-Pad2)") (class "Default")
      (node (ref "IC4") (pin "2") (pinfunction "D_2") (pintype "input"))
    )
    (net (code "174") (name "unconnected-(IC4A-PRE-Pad4)") (class "Default")
      (node (ref "IC4") (pin "4") (pinfunction "PRE_4") (pintype "input"))
    )
    (net (code "175") (name "unconnected-(IC4A-Q-Pad5)") (class "Default")
      (node (ref "IC4") (pin "5") (pinfunction "Q_5") (pintype "output"))
    )
    (net (code "176") (name "unconnected-(IC4A-~{Q}-Pad6)") (class "Default")
      (node (ref "IC4") (pin "6") (pinfunction "~{Q}_6") (pintype "output"))
    )
    (net (code "177") (name "unconnected-(IC5B-~{Q}-Pad8)") (class "Default")
      (node (ref "IC5") (pin "8") (pinfunction "~{Q}_8") (pintype "output"))
    )
    (net (code "178") (name "unconnected-(IC6A-1A-Pad2)") (class "Default")
      (node (ref "IC6") (pin "2") (pinfunction "1A_2") (pintype "input"))
    )
    (net (code "179") (name "unconnected-(IC6A-1B-Pad3)") (class "Default")
      (node (ref "IC6") (pin "3") (pinfunction "1B_3") (pintype "input"))
    )
    (net (code "180") (name "unconnected-(IC6A-1Y-Pad4)") (class "Default")
      (node (ref "IC6") (pin "4") (pinfunction "1Y_4") (pintype "output"))
    )
    (net (code "181") (name "unconnected-(IC6A-3A-Pad11)") (class "Default")
      (node (ref "IC6") (pin "11") (pinfunction "3A_11") (pintype "input"))
    )
    (net (code "182") (name "unconnected-(IC6A-3B-Pad10)") (class "Default")
      (node (ref "IC6") (pin "10") (pinfunction "3B_10") (pintype "input"))
    )
    (net (code "183") (name "unconnected-(IC6A-3Y-Pad9)") (class "Default")
      (node (ref "IC6") (pin "9") (pinfunction "3Y_9") (pintype "output"))
    )
    (net (code "184") (name "unconnected-(IC9A-1A-Pad2)") (class "Default")
      (node (ref "IC9") (pin "2") (pinfunction "1A_2") (pintype "input"))
    )
    (net (code "185") (name "unconnected-(IC9A-1B-Pad3)") (class "Default")
      (node (ref "IC9") (pin "3") (pinfunction "1B_3") (pintype "input"))
    )
    (net (code "186") (name "unconnected-(IC9A-1Y-Pad4)") (class "Default")
      (node (ref "IC9") (pin "4") (pinfunction "1Y_4") (pintype "output"))
    )
    (net (code "187") (name "unconnected-(IC12-CHA_O-Pad11)") (class "Default")
      (node (ref "IC12") (pin "11") (pinfunction "CHA_O_11") (pintype "input"))
    )
    (net (code "188") (name "unconnected-(L1B-S1-PadS2)") (class "Default")
      (node (ref "L1") (pin "S2") (pinfunction "S1_S2") (pintype "passive"))
    )
    (net (code "189") (name "unconnected-(L1B-S2-PadS1)") (class "Default")
      (node (ref "L1") (pin "S1") (pinfunction "S2_S1") (pintype "passive"))
    )
    (net (code "190") (name "unconnected-(U$1AX-EDGE-Pad28B)") (class "Default")
      (node (ref "U$1") (pin "28B") (pinfunction "EDGE_28B") (pintype "bidirectional"))
    )
    (net (code "191") (name "unconnected-(U$1F-EDGE-Pad15A)") (class "Default")
      (node (ref "U$1") (pin "15A") (pinfunction "EDGE_15A") (pintype "bidirectional"))
    )
    (net (code "192") (name "unconnected-(U$1G-EDGE-Pad16A)") (class "Default")
      (node (ref "U$1") (pin "16A") (pinfunction "EDGE_16A") (pintype "bidirectional"))
    )
    (net (code "193") (name "unconnected-(U$1H-EDGE-Pad17A)") (class "Default")
      (node (ref "U$1") (pin "17A") (pinfunction "EDGE_17A") (pintype "bidirectional"))
    )
    (net (code "194") (name "unconnected-(U$1I-EDGE-Pad18A)") (class "Default")
      (node (ref "U$1") (pin "18A") (pinfunction "EDGE_18A") (pintype "bidirectional"))
    )
    (net (code "195") (name "unconnected-(X2-PadNC)") (class "Default")
      (node (ref "X2") (pin "NC") (pinfunction "NC_NC") (pintype "passive"))
    )
  )
)
